# EVK_xA1.net
KiCad netlist of a schematic drawn in Altium Designer
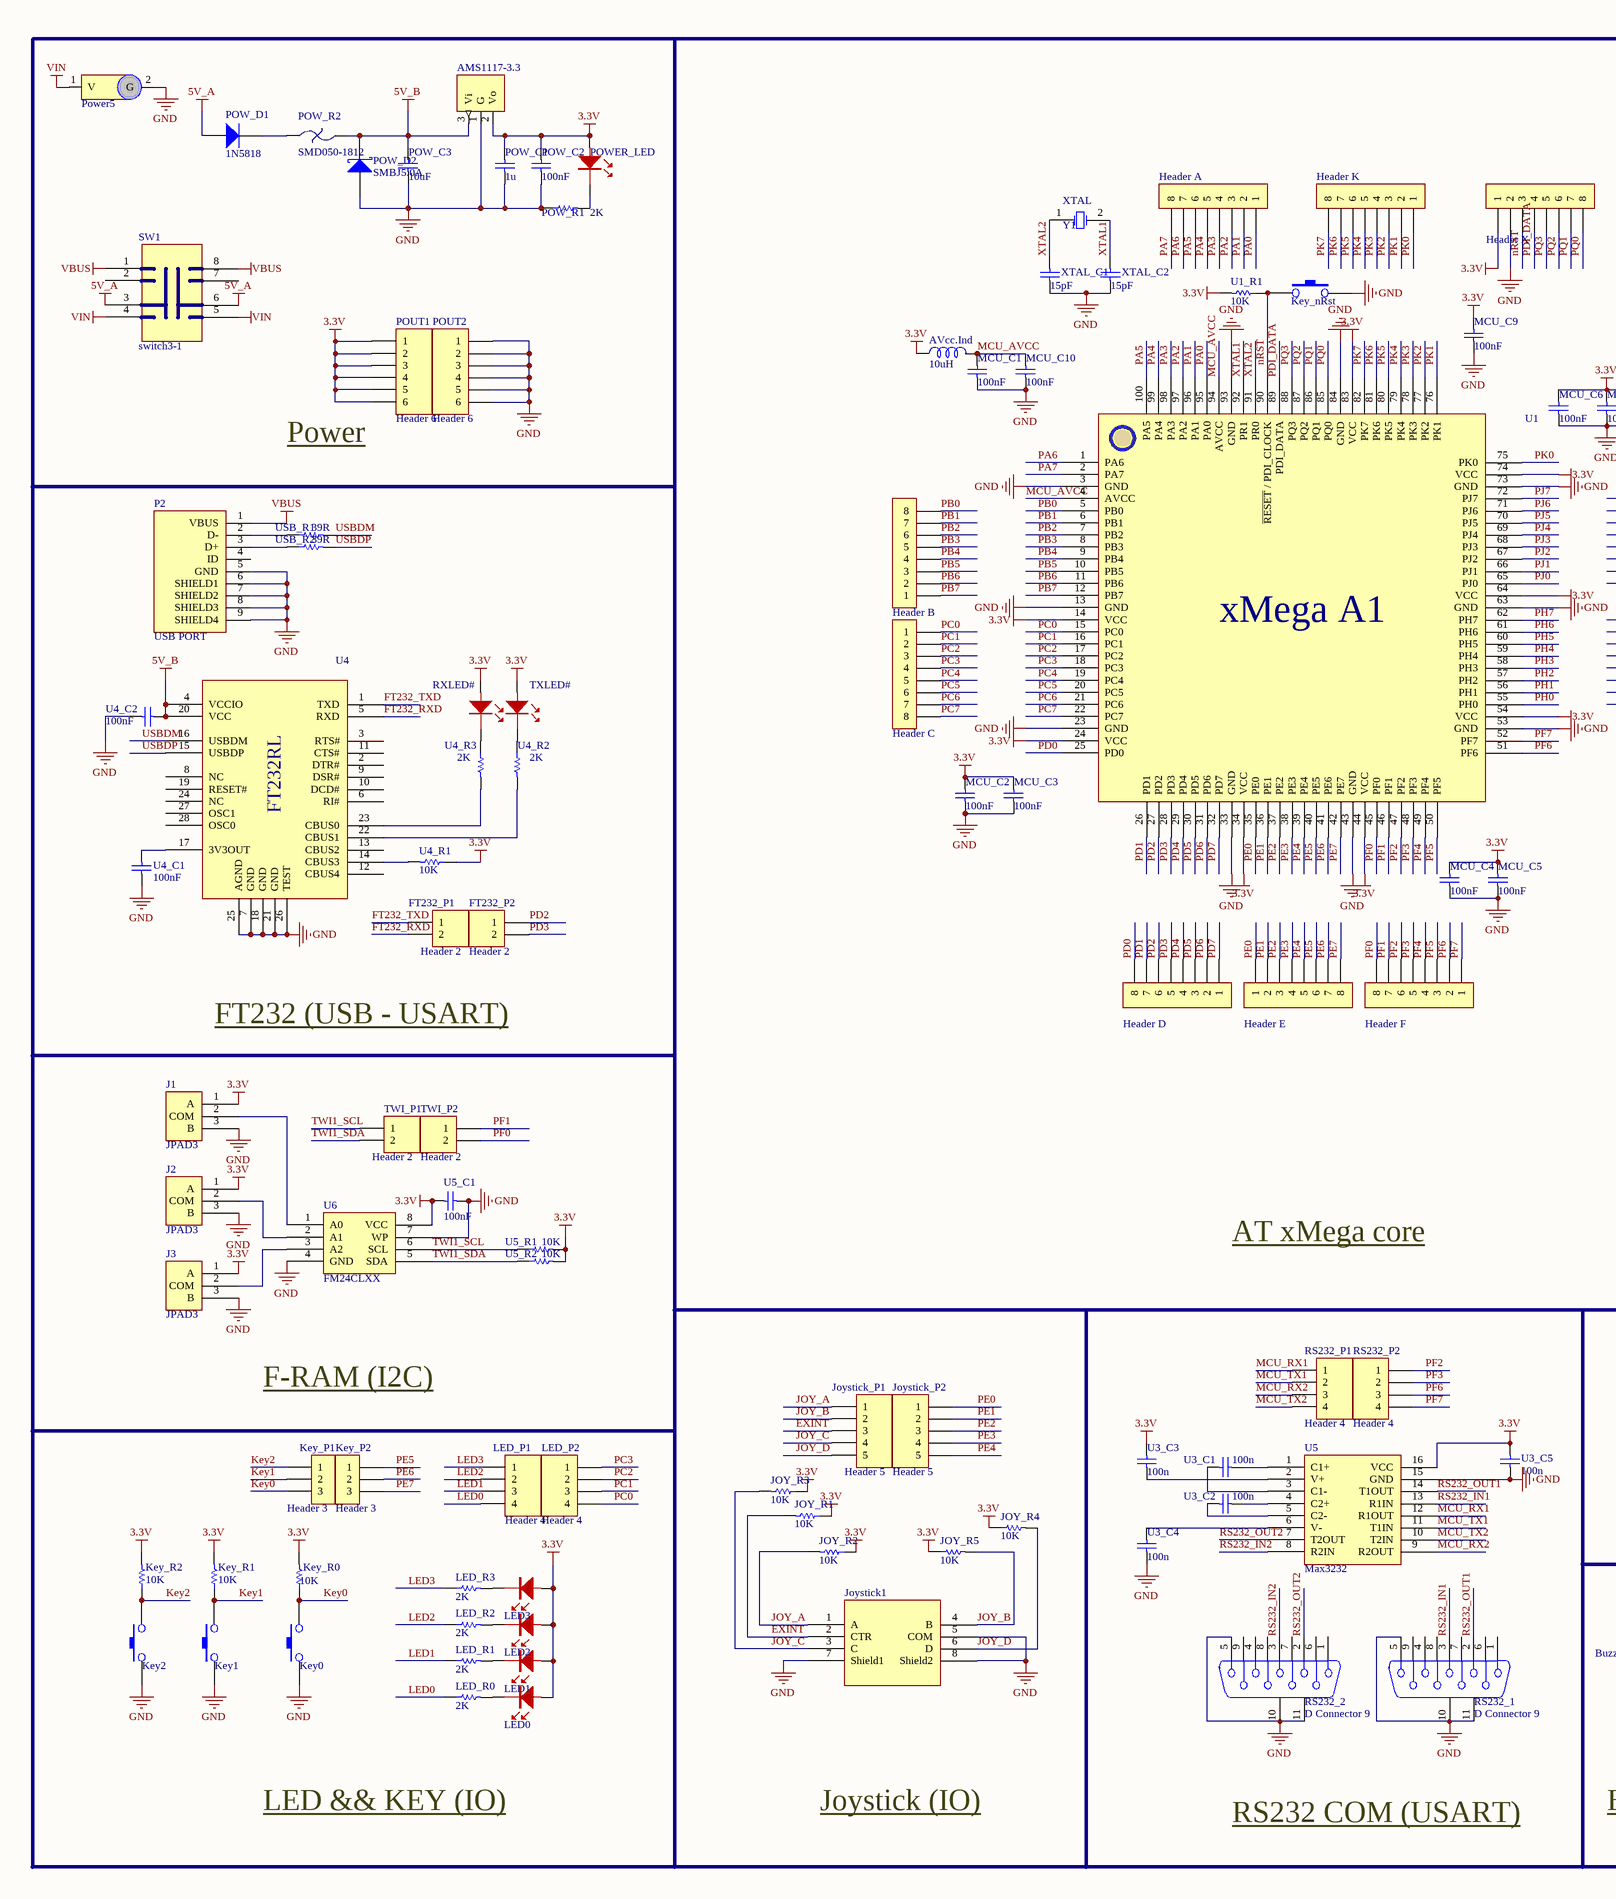
[diagram p0: EVK xA1.SchDoc, left]
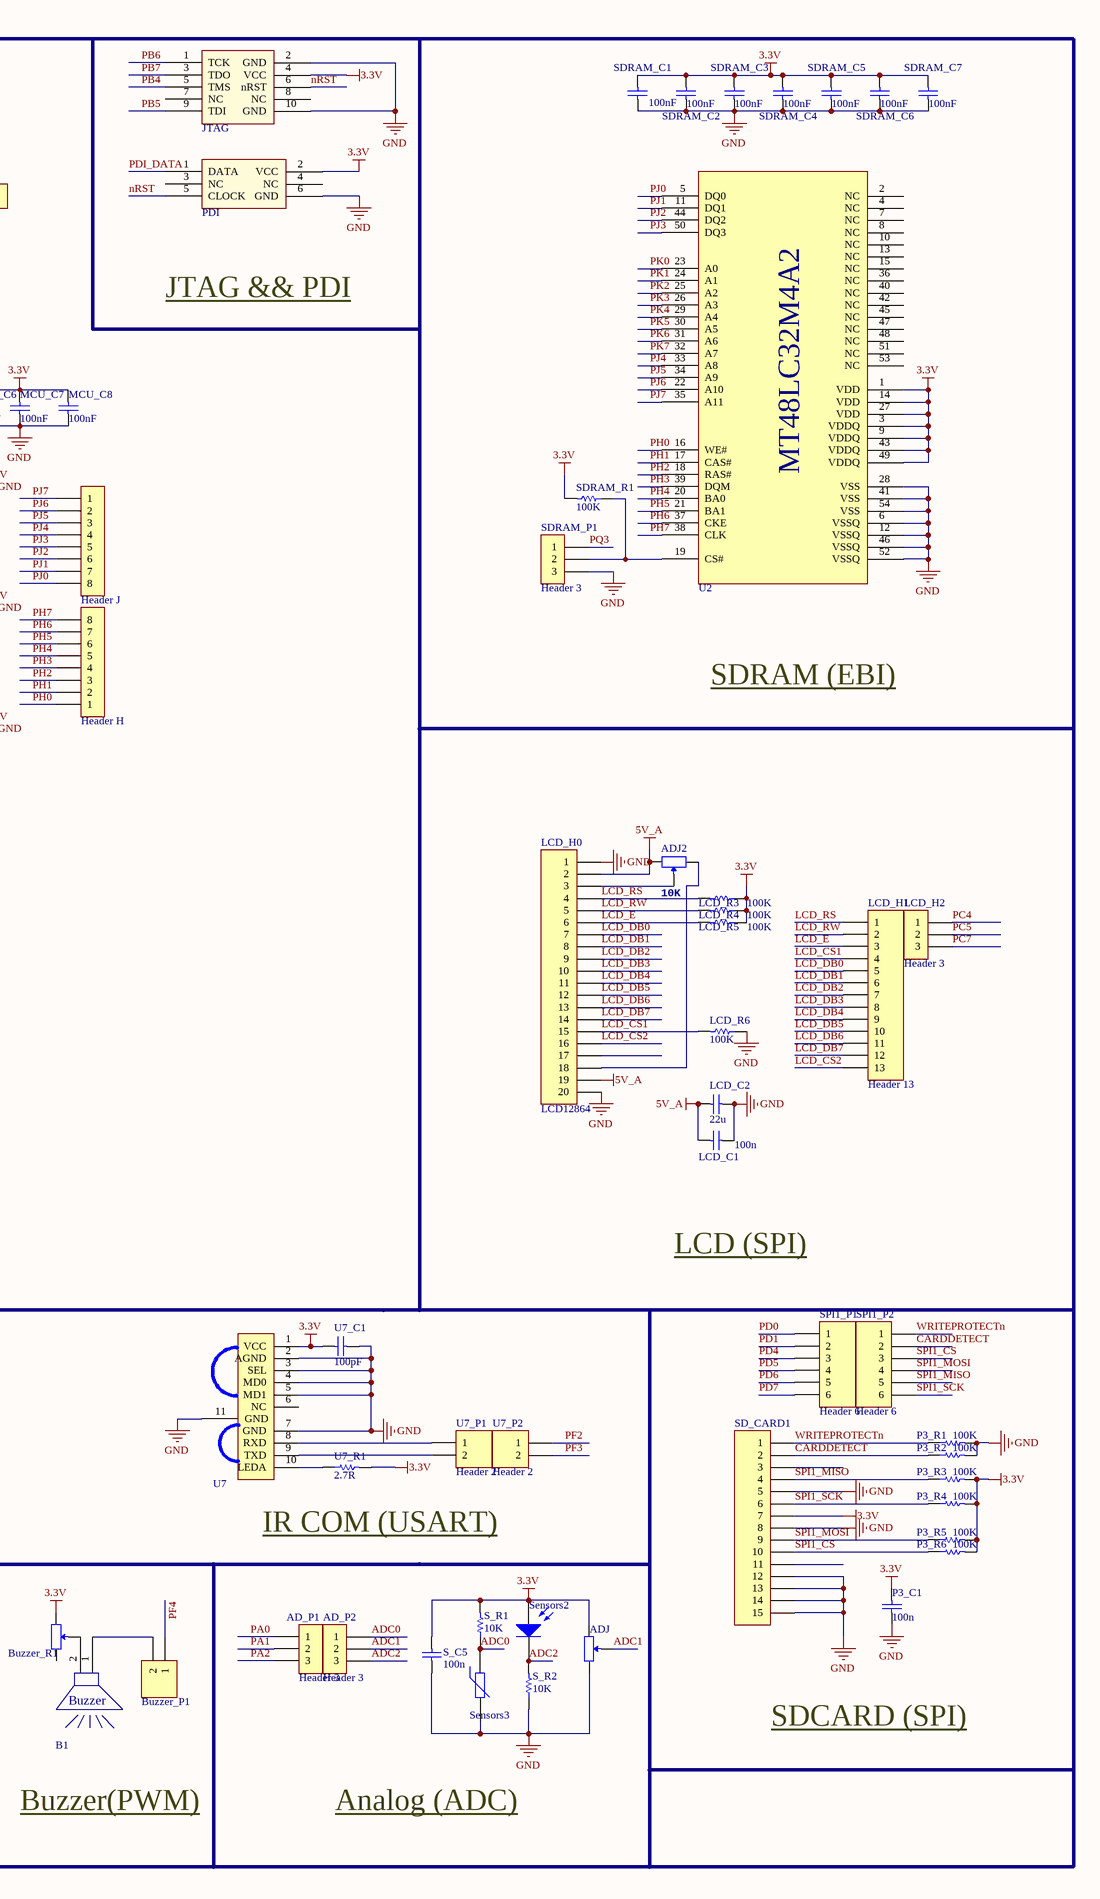
[diagram p1: EVK xA1.SchDoc, right]

(export (version "E")
  (design (tool "Eeschema 10.0.6"))
  (components
    (comp (ref "ADJ") (value "RES_ADJ") (footprint "RESADJ") (libsource (lib "zz") (part "RES_ADJ")))
    (comp (ref "ADJ2") (value "10K") (footprint "RESADJ") (libsource (lib "zz") (part "RES_ADJ")))
    (comp (ref "AD_P1")
      (value "Header 3")
      (footprint "SIP3")
      (description "Header, 3-Pin")
      (libsource (lib "") (part "Header 3_1"))
    )
    (comp (ref "AD_P2")
      (value "Header 3")
      (footprint "SIP3")
      (description "Header, 3-Pin")
      (libsource (lib "zz") (part "Header 3"))
    )
    (comp (ref "AMS1117-3.3")
      (value "LD1117")
      (footprint "LD1117-3.3")
      (libsource (lib "zz") (part "LD1117"))
    )
    (comp (ref "AVcc.Ind") (value "10uH") (footprint "RES") (libsource (lib "zz") (part "IND")))
    (comp (ref "B1") (value "Buzzer") (footprint "buzzer") (libsource (lib "zz") (part "Buzzer")))
    (comp (ref "Buzzer_P1")
      (value "Header 2")
      (footprint "SIP2")
      (description "Header, 2-Pin")
      (fields (field (name "PUBLISHER") "Altium Limited"))
      (libsource (lib "") (part "Header 2_1"))
    )
    (comp (ref "Buzzer_R1") (value "RES_ADJ") (footprint "RESADJ2") (libsource (lib "zz") (part "RES_ADJ")))
    (comp (ref "FT232_P1")
      (value "Header 2")
      (footprint "SIP2")
      (description "Header, 2-Pin")
      (fields (field (name "PUBLISHER") "Altium Limited"))
      (libsource (lib "zz") (part "Header 2"))
    )
    (comp (ref "FT232_P2")
      (value "Header 2")
      (footprint "SIP2")
      (description "Header, 2-Pin")
      (fields (field (name "PUBLISHER") "Altium Limited"))
      (libsource (lib "") (part "Header 2_1"))
    )
    (comp (ref "Header A")
      (value "Header 8")
      (footprint "SIP8")
      (description "Header, 8-Pin")
      (libsource (lib "") (part "Header 8_2"))
    )
    (comp (ref "Header B")
      (value "Header 8")
      (footprint "SIP8")
      (description "Header, 8-Pin")
      (libsource (lib "") (part "Header 8_1"))
    )
    (comp (ref "Header C")
      (value "Header 8")
      (footprint "SIP8")
      (description "Header, 8-Pin")
      (libsource (lib "") (part "Header 8_3"))
    )
    (comp (ref "Header D")
      (value "Header 8")
      (footprint "SIP8")
      (description "Header, 8-Pin")
      (libsource (lib "") (part "Header 8_3"))
    )
    (comp (ref "Header E")
      (value "Header 8")
      (footprint "SIP8")
      (description "Header, 8-Pin")
      (libsource (lib "") (part "Header 8_1"))
    )
    (comp (ref "Header F")
      (value "Header 8")
      (footprint "SIP8")
      (description "Header, 8-Pin")
      (libsource (lib "") (part "Header 8_3"))
    )
    (comp (ref "Header H")
      (value "Header 8")
      (footprint "SIP8")
      (description "Header, 8-Pin")
      (libsource (lib "zz") (part "Header 8"))
    )
    (comp (ref "Header J")
      (value "Header 8")
      (footprint "SIP8")
      (description "Header, 8-Pin")
      (libsource (lib "") (part "Header 8_2"))
    )
    (comp (ref "Header K")
      (value "Header 8")
      (footprint "SIP8")
      (description "Header, 8-Pin")
      (libsource (lib "") (part "Header 8_2"))
    )
    (comp (ref "Header X")
      (value "Header 8")
      (footprint "SIP8")
      (description "Header, 8-Pin")
      (libsource (lib "zz") (part "Header 8"))
    )
    (comp (ref "J1") (value "JPAD3") (footprint "JPAD3") (libsource (lib "zz") (part "JPAD3")))
    (comp (ref "J2") (value "JPAD3") (footprint "JPAD3") (libsource (lib "zz") (part "JPAD3")))
    (comp (ref "J3") (value "JPAD3") (footprint "JPAD3") (libsource (lib "zz") (part "JPAD3")))
    (comp (ref "Joystick1")
      (value "Joystick")
      (footprint "Joystick")
      (libsource (lib "zz") (part "Joystick"))
    )
    (comp (ref "Joystick_P1")
      (value "Header 5")
      (footprint "SIP5")
      (description "Header, 5-Pin")
      (fields (field (name "PUBLISHER") "Altium Limited"))
      (libsource (lib "zz") (part "Header 5"))
    )
    (comp (ref "Joystick_P2")
      (value "Header 5")
      (footprint "SIP5")
      (description "Header, 5-Pin")
      (fields (field (name "PUBLISHER") "Altium Limited"))
      (libsource (lib "") (part "Header 5_1"))
    )
    (comp (ref "JOY_R1")
      (value "10K")
      (footprint "0805")
      (description "Resistor")
      (fields (field (name "Comment") "R_0805"))
      (libsource (lib "zz") (part "R_0805"))
    )
    (comp (ref "JOY_R2")
      (value "10K")
      (footprint "0805")
      (description "Resistor")
      (fields (field (name "Comment") "R_0805"))
      (libsource (lib "zz") (part "R_0805"))
    )
    (comp (ref "JOY_R3")
      (value "10K")
      (footprint "0805")
      (description "Resistor")
      (fields (field (name "Comment") "R_0805"))
      (libsource (lib "zz") (part "R_0805"))
    )
    (comp (ref "JOY_R4")
      (value "10K")
      (footprint "0805")
      (description "Resistor")
      (fields (field (name "Comment") "R_0805"))
      (libsource (lib "zz") (part "R_0805"))
    )
    (comp (ref "JOY_R5")
      (value "10K")
      (footprint "0805")
      (description "Resistor")
      (fields (field (name "Comment") "R_0805"))
      (libsource (lib "zz") (part "R_0805"))
    )
    (comp (ref "JTAG") (value "JTAG") (footprint "ISP_10") (libsource (lib "zz") (part "JTAG")))
    (comp (ref "Key0") (value "PB2") (footprint "KEY") (libsource (lib "zz") (part "KEY")))
    (comp (ref "Key1") (value "PB2") (footprint "KEY") (libsource (lib "zz") (part "KEY")))
    (comp (ref "Key2") (value "PB2") (footprint "KEY") (libsource (lib "zz") (part "KEY")))
    (comp (ref "Key_nRst") (value "PB2") (footprint "KEY") (libsource (lib "zz") (part "KEY")))
    (comp (ref "Key_P1")
      (value "Header 3")
      (footprint "SIP3")
      (description "Header, 3-Pin")
      (libsource (lib "") (part "Header 3_1"))
    )
    (comp (ref "Key_P2")
      (value "Header 3")
      (footprint "SIP3")
      (description "Header, 3-Pin")
      (libsource (lib "zz") (part "Header 3"))
    )
    (comp (ref "Key_R0")
      (value "10K")
      (footprint "0805")
      (description "Resistor")
      (fields (field (name "Comment") "R_0805"))
      (libsource (lib "zz") (part "R_0805"))
    )
    (comp (ref "Key_R1")
      (value "10K")
      (footprint "0805")
      (description "Resistor")
      (fields (field (name "Comment") "R_0805"))
      (libsource (lib "zz") (part "R_0805"))
    )
    (comp (ref "Key_R2")
      (value "10K")
      (footprint "0805")
      (description "Resistor")
      (fields (field (name "Comment") "R_0805"))
      (libsource (lib "zz") (part "R_0805"))
    )
    (comp (ref "LCD_C1")
      (value "100n")
      (footprint "0805")
      (description "Capacitor")
      (fields (field (name "Comment") "C_0805"))
      (libsource (lib "zz") (part "C_0805"))
    )
    (comp (ref "LCD_C2")
      (value "22u")
      (footprint "0805")
      (description "Capacitor")
      (fields (field (name "Comment") "C_0805"))
      (libsource (lib "zz") (part "C_0805"))
    )
    (comp (ref "LCD_H0")
      (value "LCD12864")
      (footprint "SIP20")
      (description "Header, 20-Pin")
      (fields (field (name "PUBLISHER") "Altium Limited"))
      (libsource (lib "zz") (part "Header 20"))
    )
    (comp (ref "LCD_H1")
      (value "Header 13")
      (footprint "SIP13")
      (description "Header, 13-Pin")
      (fields (field (name "PUBLISHER") "Altium Limited"))
      (libsource (lib "zz") (part "Header 13"))
    )
    (comp (ref "LCD_H2")
      (value "Header 3")
      (footprint "SIP3")
      (description "Header, 3-Pin")
      (libsource (lib "zz") (part "Header 3"))
    )
    (comp (ref "LCD_R3")
      (value "100K")
      (footprint "0805")
      (description "Resistor")
      (fields (field (name "Comment") "R_0805"))
      (libsource (lib "zz") (part "R_0805"))
    )
    (comp (ref "LCD_R4")
      (value "100K")
      (footprint "0805")
      (description "Resistor")
      (fields (field (name "Comment") "R_0805"))
      (libsource (lib "zz") (part "R_0805"))
    )
    (comp (ref "LCD_R5")
      (value "100K")
      (footprint "0805")
      (description "Resistor")
      (fields (field (name "Comment") "R_0805"))
      (libsource (lib "zz") (part "R_0805"))
    )
    (comp (ref "LCD_R6")
      (value "100K")
      (footprint "0805")
      (description "Resistor")
      (fields (field (name "Comment") "R_0805"))
      (libsource (lib "zz") (part "R_0805"))
    )
    (comp (ref "LED0") (value "LED_0805") (footprint "0805_LED") (libsource (lib "zz") (part "LED_0805")))
    (comp (ref "LED1") (value "LED_0805") (footprint "0805_LED") (libsource (lib "zz") (part "LED_0805")))
    (comp (ref "LED2") (value "LED_0805") (footprint "0805_LED") (libsource (lib "zz") (part "LED_0805")))
    (comp (ref "LED3") (value "LED_0805") (footprint "0805_LED") (libsource (lib "zz") (part "LED_0805")))
    (comp (ref "LED_P1")
      (value "Header 4")
      (footprint "SIP4")
      (description "Header, 4-Pin")
      (fields (field (name "PUBLISHER") "Altium Limited"))
      (libsource (lib "zz") (part "Header 4"))
    )
    (comp (ref "LED_P2")
      (value "Header 4")
      (footprint "SIP4")
      (description "Header, 4-Pin")
      (fields (field (name "PUBLISHER") "Altium Limited"))
      (libsource (lib "") (part "Header 4_1"))
    )
    (comp (ref "LED_R0")
      (value "2K")
      (footprint "0805")
      (description "Resistor")
      (fields (field (name "Comment") "R_0805"))
      (libsource (lib "zz") (part "R_0805"))
    )
    (comp (ref "LED_R1")
      (value "2K")
      (footprint "0805")
      (description "Resistor")
      (fields (field (name "Comment") "R_0805"))
      (libsource (lib "zz") (part "R_0805"))
    )
    (comp (ref "LED_R2")
      (value "2K")
      (footprint "0805")
      (description "Resistor")
      (fields (field (name "Comment") "R_0805"))
      (libsource (lib "zz") (part "R_0805"))
    )
    (comp (ref "LED_R3")
      (value "2K")
      (footprint "0805")
      (description "Resistor")
      (fields (field (name "Comment") "R_0805"))
      (libsource (lib "zz") (part "R_0805"))
    )
    (comp (ref "MCU_C1")
      (value "100nF")
      (footprint "0805")
      (description "Capacitor")
      (fields (field (name "Comment") "C_0805"))
      (libsource (lib "zz") (part "C_0805"))
    )
    (comp (ref "MCU_C2")
      (value "100nF")
      (footprint "0805")
      (description "Capacitor")
      (fields (field (name "Comment") "C_0805"))
      (libsource (lib "zz") (part "C_0805"))
    )
    (comp (ref "MCU_C3")
      (value "100nF")
      (footprint "0805")
      (description "Capacitor")
      (fields (field (name "Comment") "C_0805"))
      (libsource (lib "zz") (part "C_0805"))
    )
    (comp (ref "MCU_C4")
      (value "100nF")
      (footprint "0805")
      (description "Capacitor")
      (fields (field (name "Comment") "C_0805"))
      (libsource (lib "zz") (part "C_0805"))
    )
    (comp (ref "MCU_C5")
      (value "100nF")
      (footprint "0805")
      (description "Capacitor")
      (fields (field (name "Comment") "C_0805"))
      (libsource (lib "zz") (part "C_0805"))
    )
    (comp (ref "MCU_C6")
      (value "100nF")
      (footprint "0805")
      (description "Capacitor")
      (fields (field (name "Comment") "C_0805"))
      (libsource (lib "zz") (part "C_0805"))
    )
    (comp (ref "MCU_C7")
      (value "100nF")
      (footprint "0805")
      (description "Capacitor")
      (fields (field (name "Comment") "C_0805"))
      (libsource (lib "zz") (part "C_0805"))
    )
    (comp (ref "MCU_C8")
      (value "100nF")
      (footprint "0805")
      (description "Capacitor")
      (fields (field (name "Comment") "C_0805"))
      (libsource (lib "zz") (part "C_0805"))
    )
    (comp (ref "MCU_C9")
      (value "100nF")
      (footprint "0805")
      (description "Capacitor")
      (fields (field (name "Comment") "C_0805"))
      (libsource (lib "zz") (part "C_0805"))
    )
    (comp (ref "MCU_C10")
      (value "100nF")
      (footprint "0805")
      (description "Capacitor")
      (fields (field (name "Comment") "C_0805"))
      (libsource (lib "zz") (part "C_0805"))
    )
    (comp (ref "P2") (value "USB PORT") (footprint "USB2") (libsource (lib "zz") (part "USB")))
    (comp (ref "P3_C1")
      (value "100n")
      (footprint "0805")
      (description "Capacitor")
      (fields (field (name "Comment") "C_0805"))
      (libsource (lib "zz") (part "C_0805"))
    )
    (comp (ref "P3_R1")
      (value "100K")
      (footprint "0805")
      (description "Resistor")
      (fields (field (name "Comment") "R_0805"))
      (libsource (lib "zz") (part "R_0805"))
    )
    (comp (ref "P3_R2")
      (value "100K")
      (footprint "0805")
      (description "Resistor")
      (fields (field (name "Comment") "R_0805"))
      (libsource (lib "zz") (part "R_0805"))
    )
    (comp (ref "P3_R3")
      (value "100K")
      (footprint "0805")
      (description "Resistor")
      (fields (field (name "Comment") "R_0805"))
      (libsource (lib "zz") (part "R_0805"))
    )
    (comp (ref "P3_R4")
      (value "100K")
      (footprint "0805")
      (description "Resistor")
      (fields (field (name "Comment") "R_0805"))
      (libsource (lib "zz") (part "R_0805"))
    )
    (comp (ref "P3_R5")
      (value "100K")
      (footprint "0805")
      (description "Resistor")
      (fields (field (name "Comment") "R_0805"))
      (libsource (lib "zz") (part "R_0805"))
    )
    (comp (ref "P3_R6")
      (value "100K")
      (footprint "0805")
      (description "Resistor")
      (fields (field (name "Comment") "R_0805"))
      (libsource (lib "zz") (part "R_0805"))
    )
    (comp (ref "PDI") (value "PDI") (footprint "ISP_6") (libsource (lib "zz") (part "PDI")))
    (comp (ref "POUT1")
      (value "Header 6")
      (footprint "SIP6")
      (description "Header, 6-Pin")
      (fields (field (name "PUBLISHER") "Altium Limited"))
      (libsource (lib "") (part "Header 6_1"))
    )
    (comp (ref "POUT2")
      (value "Header 6")
      (footprint "SIP6")
      (description "Header, 6-Pin")
      (fields (field (name "PUBLISHER") "Altium Limited"))
      (libsource (lib "zz") (part "Header 6"))
    )
    (comp (ref "Power5")
      (value "5V")
      (footprint "PWR_5V")
      (description "Power5")
      (libsource (lib "zz") (part "Power5"))
    )
    (comp (ref "POWER_LED")
      (value "LED_0805")
      (footprint "0805_LED")
      (libsource (lib "zz") (part "LED_0805"))
    )
    (comp (ref "POW_C1")
      (value "1u")
      (footprint "0805")
      (description "Capacitor")
      (fields (field (name "Comment") "C_0805"))
      (libsource (lib "zz") (part "C_0805"))
    )
    (comp (ref "POW_C2")
      (value "100nF")
      (footprint "0805")
      (description "Capacitor")
      (fields (field (name "Comment") "C_0805"))
      (libsource (lib "zz") (part "C_0805"))
    )
    (comp (ref "POW_C3")
      (value "10uF")
      (footprint "0805")
      (description "Capacitor")
      (fields (field (name "Comment") "C_0805"))
      (libsource (lib "zz") (part "C_0805"))
    )
    (comp (ref "POW_D1")
      (value "1N5818")
      (footprint "diode")
      (description "1 Amp General Purpose Rectifier")
      (libsource (lib "zz") (part "Diode 1N"))
    )
    (comp (ref "POW_D2") (value "SMBJ5.0A") (footprint "SMBJ") (libsource (lib "zz") (part "SMBJ5.0A")))
    (comp (ref "POW_R1")
      (value "2K")
      (footprint "0805")
      (description "Resistor")
      (fields (field (name "Comment") "R_0805"))
      (libsource (lib "zz") (part "R_0805"))
    )
    (comp (ref "POW_R2")
      (value "SMD050-1812")
      (footprint "SMD-1812")
      (libsource (lib "zz") (part "SMD050-1812"))
    )
    (comp (ref "RS232_1")
      (value "D Connector 9")
      (footprint "DB9_2")
      (description "Receptacle Assembly, 9 Position, Right Angle")
      (libsource (lib "zz") (part "D Connector 9"))
    )
    (comp (ref "RS232_2")
      (value "D Connector 9")
      (footprint "DB9_2")
      (description "Receptacle Assembly, 9 Position, Right Angle")
      (libsource (lib "zz") (part "D Connector 9"))
    )
    (comp (ref "RS232_P1")
      (value "Header 4")
      (footprint "SIP4")
      (description "Header, 4-Pin")
      (fields (field (name "PUBLISHER") "Altium Limited"))
      (libsource (lib "zz") (part "Header 4"))
    )
    (comp (ref "RS232_P2")
      (value "Header 4")
      (footprint "SIP4")
      (description "Header, 4-Pin")
      (fields (field (name "PUBLISHER") "Altium Limited"))
      (libsource (lib "") (part "Header 4_1"))
    )
    (comp (ref "RXLED#") (value "LED_0805") (footprint "0805_LED") (libsource (lib "zz") (part "LED_0805")))
    (comp (ref "SDRAM_C1")
      (value "100nF")
      (footprint "0805")
      (description "Capacitor")
      (fields (field (name "Comment") "C_0805"))
      (libsource (lib "zz") (part "C_0805"))
    )
    (comp (ref "SDRAM_C2")
      (value "100nF")
      (footprint "0805")
      (description "Capacitor")
      (fields (field (name "Comment") "C_0805"))
      (libsource (lib "zz") (part "C_0805"))
    )
    (comp (ref "SDRAM_C3")
      (value "100nF")
      (footprint "0805")
      (description "Capacitor")
      (fields (field (name "Comment") "C_0805"))
      (libsource (lib "zz") (part "C_0805"))
    )
    (comp (ref "SDRAM_C4")
      (value "100nF")
      (footprint "0805")
      (description "Capacitor")
      (fields (field (name "Comment") "C_0805"))
      (libsource (lib "zz") (part "C_0805"))
    )
    (comp (ref "SDRAM_C5")
      (value "100nF")
      (footprint "0805")
      (description "Capacitor")
      (fields (field (name "Comment") "C_0805"))
      (libsource (lib "zz") (part "C_0805"))
    )
    (comp (ref "SDRAM_C6")
      (value "100nF")
      (footprint "0805")
      (description "Capacitor")
      (fields (field (name "Comment") "C_0805"))
      (libsource (lib "zz") (part "C_0805"))
    )
    (comp (ref "SDRAM_C7")
      (value "100nF")
      (footprint "0805")
      (description "Capacitor")
      (fields (field (name "Comment") "C_0805"))
      (libsource (lib "zz") (part "C_0805"))
    )
    (comp (ref "SDRAM_P1")
      (value "Header 3")
      (footprint "SIP3")
      (description "Header, 3-Pin")
      (libsource (lib "zz") (part "Header 3"))
    )
    (comp (ref "SDRAM_R1")
      (value "100K")
      (footprint "0805")
      (description "Resistor")
      (fields (field (name "Comment") "R_0603"))
      (libsource (lib "zz") (part "R_0603"))
    )
    (comp (ref "SD_CARD1")
      (value "SDCARD")
      (footprint "SDK")
      (description "Header, 15-Pin")
      (libsource (lib "zz") (part "SDCARD"))
    )
    (comp (ref "Sensors2")
      (value "Photo Sen")
      (footprint "LED")
      (description "Photosensitive Diode")
      (libsource (lib "Miscellaneous Devices") (part "Photo Sen"))
    )
    (comp (ref "Sensors3")
      (value "Res Varistor")
      (footprint "diode")
      (description "Varistor (Voltage-Sensitive Resistor)")
      (libsource (lib "Miscellaneous Devices") (part "Res Varistor"))
    )
    (comp (ref "SPI1_P1")
      (value "Header 6")
      (footprint "SIP6")
      (description "Header, 6-Pin")
      (fields (field (name "PUBLISHER") "Altium Limited"))
      (libsource (lib "") (part "Header 6_1"))
    )
    (comp (ref "SPI1_P2")
      (value "Header 6")
      (footprint "SIP6")
      (description "Header, 6-Pin")
      (fields (field (name "PUBLISHER") "Altium Limited"))
      (libsource (lib "zz") (part "Header 6"))
    )
    (comp (ref "SW1") (value "switch3-1") (footprint "Switch3-1") (libsource (lib "zz") (part "switch3-1")))
    (comp (ref "S_C5")
      (value "100n")
      (footprint "0805")
      (description "Capacitor")
      (fields (field (name "Comment") "C_0805"))
      (libsource (lib "zz") (part "C_0805"))
    )
    (comp (ref "S_R1")
      (value "10K")
      (footprint "0805")
      (description "Resistor")
      (fields (field (name "Comment") "R_0805"))
      (libsource (lib "zz") (part "R_0805"))
    )
    (comp (ref "S_R2")
      (value "10K")
      (footprint "0805")
      (description "Resistor")
      (fields (field (name "Comment") "R_0805"))
      (libsource (lib "zz") (part "R_0805"))
    )
    (comp (ref "TWI_P1")
      (value "Header 2")
      (footprint "SIP2")
      (description "Header, 2-Pin")
      (fields (field (name "PUBLISHER") "Altium Limited"))
      (libsource (lib "zz") (part "Header 2"))
    )
    (comp (ref "TWI_P2")
      (value "Header 2")
      (footprint "SIP2")
      (description "Header, 2-Pin")
      (fields (field (name "PUBLISHER") "Altium Limited"))
      (libsource (lib "") (part "Header 2_1"))
    )
    (comp (ref "TXLED#") (value "LED_0805") (footprint "0805_LED") (libsource (lib "zz") (part "LED_0805")))
    (comp (ref "U1") (value "xMega A1") (footprint "TQFP100 CORE") (libsource (lib "zz") (part "xMega A1")))
    (comp (ref "U1_R1")
      (value "10K")
      (footprint "0805")
      (description "Resistor")
      (fields (field (name "Comment") "R_0805"))
      (libsource (lib "zz") (part "R_0805"))
    )
    (comp (ref "U2") (value "MT48LC32M4A2") (footprint "TSOP54") (libsource (lib "zz") (part "MT48LC32M4A2")))
    (comp (ref "U3_C1")
      (value "100n")
      (footprint "0805")
      (description "Capacitor")
      (fields (field (name "Comment") "C_0805"))
      (libsource (lib "zz") (part "C_0805"))
    )
    (comp (ref "U3_C2")
      (value "100n")
      (footprint "0805")
      (description "Capacitor")
      (fields (field (name "Comment") "C_0805"))
      (libsource (lib "zz") (part "C_0805"))
    )
    (comp (ref "U3_C3")
      (value "100n")
      (footprint "0805")
      (description "Capacitor")
      (fields (field (name "Comment") "C_0805"))
      (libsource (lib "zz") (part "C_0805"))
    )
    (comp (ref "U3_C4")
      (value "100n")
      (footprint "0805")
      (description "Capacitor")
      (fields (field (name "Comment") "C_0805"))
      (libsource (lib "zz") (part "C_0805"))
    )
    (comp (ref "U3_C5")
      (value "100n")
      (footprint "0805")
      (description "Capacitor")
      (fields (field (name "Comment") "C_0805"))
      (libsource (lib "zz") (part "C_0805"))
    )
    (comp (ref "U4") (value "FT232RL") (footprint "SSOP28") (libsource (lib "zz") (part "FT232RL")))
    (comp (ref "U4_C1")
      (value "100nF")
      (footprint "0805")
      (description "Capacitor")
      (fields (field (name "Comment") "C_0805"))
      (libsource (lib "zz") (part "C_0805"))
    )
    (comp (ref "U4_C2")
      (value "100nF")
      (footprint "0805")
      (description "Capacitor")
      (fields (field (name "Comment") "C_0805"))
      (libsource (lib "zz") (part "C_0805"))
    )
    (comp (ref "U4_R1")
      (value "10K")
      (footprint "0805")
      (description "Resistor")
      (fields (field (name "Comment") "R_0805"))
      (libsource (lib "zz") (part "R_0805"))
    )
    (comp (ref "U4_R2")
      (value "2K")
      (footprint "0805")
      (description "Resistor")
      (fields (field (name "Comment") "R_0805"))
      (libsource (lib "zz") (part "R_0805"))
    )
    (comp (ref "U4_R3")
      (value "2K")
      (footprint "0805")
      (description "Resistor")
      (fields (field (name "Comment") "R_0805"))
      (libsource (lib "zz") (part "R_0805"))
    )
    (comp (ref "U5") (value "Max3232") (footprint "SOP16") (libsource (lib "zz") (part "Max3232")))
    (comp (ref "U5_C1")
      (value "100nF")
      (footprint "0805")
      (description "Capacitor")
      (fields (field (name "Comment") "C_0805"))
      (libsource (lib "zz") (part "C_0805"))
    )
    (comp (ref "U5_R1")
      (value "10K")
      (footprint "0805")
      (description "Resistor")
      (fields (field (name "Comment") "R_0805"))
      (libsource (lib "zz") (part "R_0805"))
    )
    (comp (ref "U5_R2")
      (value "10K")
      (footprint "0805")
      (description "Resistor")
      (fields (field (name "Comment") "R_0805"))
      (libsource (lib "zz") (part "R_0805"))
    )
    (comp (ref "U6") (value "FM24CLXX") (footprint "AT24C") (libsource (lib "zz") (part "AT24C")))
    (comp (ref "U7")
      (value "HSDL-3602-007")
      (footprint "HSDL-3602-007")
      (libsource (lib "zz") (part "HSDL-3602-007"))
    )
    (comp (ref "U7_C1")
      (value "100pF")
      (footprint "0805")
      (description "Capacitor")
      (fields (field (name "Comment") "C_0805"))
      (libsource (lib "zz") (part "C_0805"))
    )
    (comp (ref "U7_P1")
      (value "Header 2")
      (footprint "SIP2")
      (description "Header, 2-Pin")
      (fields (field (name "PUBLISHER") "Altium Limited"))
      (libsource (lib "zz") (part "Header 2"))
    )
    (comp (ref "U7_P2")
      (value "Header 2")
      (footprint "SIP2")
      (description "Header, 2-Pin")
      (fields (field (name "PUBLISHER") "Altium Limited"))
      (libsource (lib "") (part "Header 2_1"))
    )
    (comp (ref "U7_R1")
      (value "2.7R")
      (footprint "0805")
      (description "Resistor")
      (fields (field (name "Comment") "R_0805"))
      (libsource (lib "zz") (part "R_0805"))
    )
    (comp (ref "USB_R1")
      (value "39R")
      (footprint "0805")
      (description "Resistor")
      (fields (field (name "Comment") "R_0805"))
      (libsource (lib "zz") (part "R_0805"))
    )
    (comp (ref "USB_R2")
      (value "39R")
      (footprint "0805")
      (description "Resistor")
      (fields (field (name "Comment") "R_0805"))
      (libsource (lib "zz") (part "R_0805"))
    )
    (comp (ref "XTAL_C1")
      (value "15pF")
      (footprint "0805")
      (description "Capacitor")
      (fields (field (name "Comment") "Cap"))
      (libsource (lib "Miscellaneous Devices") (part "Cap"))
    )
    (comp (ref "XTAL_C2")
      (value "15pF")
      (footprint "0805")
      (description "Capacitor")
      (fields (field (name "Comment") "Cap"))
      (libsource (lib "Miscellaneous Devices") (part "Cap"))
    )
    (comp (ref "Y1")
      (value "XTAL")
      (footprint "CRYSTAL")
      (description "Crystal Oscillator")
      (fields (field (name "PUBLISHER") "Altium Limited"))
      (libsource (lib "zz") (part "XTAL"))
    )
  )
  (nets
    (net (code "1") (name "/ADC0") (class "Default")
      (node (ref "AD_P2") (pin "1") (pinfunction "1_1") (pintype "passive"))
      (node (ref "S_R1") (pin "1") (pinfunction "1_1") (pintype "passive"))
      (node (ref "Sensors3") (pin "1") (pinfunction "1_1") (pintype "passive"))
    )
    (net (code "2") (name "/ADC1") (class "Default")
      (node (ref "ADJ") (pin "2") (pinfunction "TAP_2") (pintype "passive"))
      (node (ref "AD_P2") (pin "2") (pinfunction "2_2") (pintype "passive"))
    )
    (net (code "3") (name "/ADC2") (class "Default")
      (node (ref "AD_P2") (pin "3") (pinfunction "3_3") (pintype "passive"))
      (node (ref "S_R2") (pin "2") (pinfunction "2_2") (pintype "passive"))
      (node (ref "Sensors2") (pin "2") (pinfunction "K_2") (pintype "passive"))
    )
    (net (code "4") (name "/CARDDETECT") (class "Default")
      (node (ref "P3_R2") (pin "1") (pinfunction "1_1") (pintype "passive"))
      (node (ref "SD_CARD1") (pin "2") (pinfunction "2_2") (pintype "passive"))
      (node (ref "SPI1_P2") (pin "2") (pinfunction "2_2") (pintype "passive"))
    )
    (net (code "5") (name "/EXINT") (class "Default")
      (node (ref "JOY_R1") (pin "2") (pinfunction "2_2") (pintype "passive"))
      (node (ref "Joystick1") (pin "2") (pinfunction "CTR_2") (pintype "passive"))
      (node (ref "Joystick_P1") (pin "3") (pinfunction "3_3") (pintype "passive"))
    )
    (net (code "6") (name "/FT232_RXD") (class "Default")
      (node (ref "FT232_P1") (pin "2") (pinfunction "2_2") (pintype "passive"))
      (node (ref "U4") (pin "5") (pinfunction "RXD_5") (pintype "passive"))
    )
    (net (code "7") (name "/FT232_TXD") (class "Default")
      (node (ref "FT232_P1") (pin "1") (pinfunction "1_1") (pintype "passive"))
      (node (ref "U4") (pin "1") (pinfunction "TXD_1") (pintype "passive"))
    )
    (net (code "8") (name "/JOY_A") (class "Default")
      (node (ref "JOY_R2") (pin "2") (pinfunction "2_2") (pintype "passive"))
      (node (ref "Joystick1") (pin "1") (pinfunction "A_1") (pintype "passive"))
      (node (ref "Joystick_P1") (pin "1") (pinfunction "1_1") (pintype "passive"))
    )
    (net (code "9") (name "/JOY_B") (class "Default")
      (node (ref "JOY_R5") (pin "2") (pinfunction "2_2") (pintype "passive"))
      (node (ref "Joystick1") (pin "4") (pinfunction "B_4") (pintype "passive"))
      (node (ref "Joystick_P1") (pin "2") (pinfunction "2_2") (pintype "passive"))
    )
    (net (code "10") (name "/JOY_C") (class "Default")
      (node (ref "JOY_R3") (pin "2") (pinfunction "2_2") (pintype "passive"))
      (node (ref "Joystick1") (pin "3") (pinfunction "C_3") (pintype "passive"))
      (node (ref "Joystick_P1") (pin "4") (pinfunction "4_4") (pintype "passive"))
    )
    (net (code "11") (name "/JOY_D") (class "Default")
      (node (ref "JOY_R4") (pin "2") (pinfunction "2_2") (pintype "passive"))
      (node (ref "Joystick1") (pin "6") (pinfunction "D_6") (pintype "passive"))
      (node (ref "Joystick_P1") (pin "5") (pinfunction "5_5") (pintype "passive"))
    )
    (net (code "12") (name "/Key0") (class "Default")
      (node (ref "Key0") (pin "2") (pinfunction "2_2") (pintype "passive"))
      (node (ref "Key_P1") (pin "3") (pinfunction "3_3") (pintype "passive"))
      (node (ref "Key_R0") (pin "1") (pinfunction "1_1") (pintype "passive"))
    )
    (net (code "13") (name "/Key1") (class "Default")
      (node (ref "Key1") (pin "2") (pinfunction "2_2") (pintype "passive"))
      (node (ref "Key_P1") (pin "2") (pinfunction "2_2") (pintype "passive"))
      (node (ref "Key_R1") (pin "1") (pinfunction "1_1") (pintype "passive"))
    )
    (net (code "14") (name "/Key2") (class "Default")
      (node (ref "Key2") (pin "2") (pinfunction "2_2") (pintype "passive"))
      (node (ref "Key_P1") (pin "1") (pinfunction "1_1") (pintype "passive"))
      (node (ref "Key_R2") (pin "1") (pinfunction "1_1") (pintype "passive"))
    )
    (net (code "15") (name "/LCD_CS1") (class "Default")
      (node (ref "LCD_H0") (pin "15") (pinfunction "15_15") (pintype "passive"))
      (node (ref "LCD_H1") (pin "4") (pinfunction "4_4") (pintype "passive"))
      (node (ref "LCD_R6") (pin "2") (pinfunction "2_2") (pintype "passive"))
    )
    (net (code "16") (name "/LCD_CS2") (class "Default")
      (node (ref "LCD_H0") (pin "16") (pinfunction "16_16") (pintype "passive"))
      (node (ref "LCD_H1") (pin "13") (pinfunction "13_13") (pintype "passive"))
    )
    (net (code "17") (name "/LCD_DB0") (class "Default")
      (node (ref "LCD_H0") (pin "7") (pinfunction "7_7") (pintype "passive"))
      (node (ref "LCD_H1") (pin "5") (pinfunction "5_5") (pintype "passive"))
    )
    (net (code "18") (name "/LCD_DB1") (class "Default")
      (node (ref "LCD_H0") (pin "8") (pinfunction "8_8") (pintype "passive"))
      (node (ref "LCD_H1") (pin "6") (pinfunction "6_6") (pintype "passive"))
    )
    (net (code "19") (name "/LCD_DB2") (class "Default")
      (node (ref "LCD_H0") (pin "9") (pinfunction "9_9") (pintype "passive"))
      (node (ref "LCD_H1") (pin "7") (pinfunction "7_7") (pintype "passive"))
    )
    (net (code "20") (name "/LCD_DB3") (class "Default")
      (node (ref "LCD_H0") (pin "10") (pinfunction "10_10") (pintype "passive"))
      (node (ref "LCD_H1") (pin "8") (pinfunction "8_8") (pintype "passive"))
    )
    (net (code "21") (name "/LCD_DB4") (class "Default")
      (node (ref "LCD_H0") (pin "11") (pinfunction "11_11") (pintype "passive"))
      (node (ref "LCD_H1") (pin "9") (pinfunction "9_9") (pintype "passive"))
    )
    (net (code "22") (name "/LCD_DB5") (class "Default")
      (node (ref "LCD_H0") (pin "12") (pinfunction "12_12") (pintype "passive"))
      (node (ref "LCD_H1") (pin "10") (pinfunction "10_10") (pintype "passive"))
    )
    (net (code "23") (name "/LCD_DB6") (class "Default")
      (node (ref "LCD_H0") (pin "13") (pinfunction "13_13") (pintype "passive"))
      (node (ref "LCD_H1") (pin "11") (pinfunction "11_11") (pintype "passive"))
    )
    (net (code "24") (name "/LCD_DB7") (class "Default")
      (node (ref "LCD_H0") (pin "14") (pinfunction "14_14") (pintype "passive"))
      (node (ref "LCD_H1") (pin "12") (pinfunction "12_12") (pintype "passive"))
    )
    (net (code "25") (name "/LCD_E") (class "Default")
      (node (ref "LCD_H0") (pin "6") (pinfunction "6_6") (pintype "passive"))
      (node (ref "LCD_H1") (pin "3") (pinfunction "3_3") (pintype "passive"))
      (node (ref "LCD_R5") (pin "2") (pinfunction "2_2") (pintype "passive"))
    )
    (net (code "26") (name "/LCD_RS") (class "Default")
      (node (ref "LCD_H0") (pin "4") (pinfunction "4_4") (pintype "passive"))
      (node (ref "LCD_H1") (pin "1") (pinfunction "1_1") (pintype "passive"))
      (node (ref "LCD_R3") (pin "2") (pinfunction "2_2") (pintype "passive"))
    )
    (net (code "27") (name "/LCD_RW") (class "Default")
      (node (ref "LCD_H0") (pin "5") (pinfunction "5_5") (pintype "passive"))
      (node (ref "LCD_H1") (pin "2") (pinfunction "2_2") (pintype "passive"))
      (node (ref "LCD_R4") (pin "2") (pinfunction "2_2") (pintype "passive"))
    )
    (net (code "28") (name "/LED0") (class "Default")
      (node (ref "LED_P1") (pin "4") (pinfunction "4_4") (pintype "passive"))
      (node (ref "LED_R0") (pin "1") (pinfunction "1_1") (pintype "passive"))
    )
    (net (code "29") (name "/LED1") (class "Default")
      (node (ref "LED_P1") (pin "3") (pinfunction "3_3") (pintype "passive"))
      (node (ref "LED_R1") (pin "1") (pinfunction "1_1") (pintype "passive"))
    )
    (net (code "30") (name "/LED2") (class "Default")
      (node (ref "LED_P1") (pin "2") (pinfunction "2_2") (pintype "passive"))
      (node (ref "LED_R2") (pin "1") (pinfunction "1_1") (pintype "passive"))
    )
    (net (code "31") (name "/LED3") (class "Default")
      (node (ref "LED_P1") (pin "1") (pinfunction "1_1") (pintype "passive"))
      (node (ref "LED_R3") (pin "1") (pinfunction "1_1") (pintype "passive"))
    )
    (net (code "32") (name "/MCU_AVCC") (class "Default")
      (node (ref "AVcc.Ind") (pin "2") (pinfunction "1_2") (pintype "passive"))
      (node (ref "MCU_C1") (pin "2") (pinfunction "2_2") (pintype "passive"))
      (node (ref "MCU_C10") (pin "2") (pinfunction "2_2") (pintype "passive"))
      (node (ref "U1") (pin "4") (pinfunction "AVCC_4") (pintype "passive"))
      (node (ref "U1") (pin "94") (pinfunction "AVCC_94") (pintype "passive"))
    )
    (net (code "33") (name "/MCU_RX1") (class "Default")
      (node (ref "RS232_P1") (pin "1") (pinfunction "1_1") (pintype "passive"))
      (node (ref "U5") (pin "12") (pinfunction "R1OUT_12") (pintype "passive"))
    )
    (net (code "34") (name "/MCU_RX2") (class "Default")
      (node (ref "RS232_P1") (pin "3") (pinfunction "3_3") (pintype "passive"))
      (node (ref "U5") (pin "9") (pinfunction "R2OUT_9") (pintype "passive"))
    )
    (net (code "35") (name "/MCU_TX1") (class "Default")
      (node (ref "RS232_P1") (pin "2") (pinfunction "2_2") (pintype "passive"))
      (node (ref "U5") (pin "11") (pinfunction "T1IN_11") (pintype "passive"))
    )
    (net (code "36") (name "/MCU_TX2") (class "Default")
      (node (ref "RS232_P1") (pin "4") (pinfunction "4_4") (pintype "passive"))
      (node (ref "U5") (pin "10") (pinfunction "T2IN_10") (pintype "passive"))
    )
    (net (code "37") (name "/PA0") (class "Default")
      (node (ref "AD_P1") (pin "1") (pinfunction "1_1") (pintype "passive"))
      (node (ref "Header A") (pin "1") (pinfunction "1_1") (pintype "passive"))
      (node (ref "U1") (pin "95") (pinfunction "PA0_95") (pintype "passive"))
    )
    (net (code "38") (name "/PA1") (class "Default")
      (node (ref "AD_P1") (pin "2") (pinfunction "2_2") (pintype "passive"))
      (node (ref "Header A") (pin "2") (pinfunction "2_2") (pintype "passive"))
      (node (ref "U1") (pin "96") (pinfunction "PA1_96") (pintype "passive"))
    )
    (net (code "39") (name "/PA2") (class "Default")
      (node (ref "AD_P1") (pin "3") (pinfunction "3_3") (pintype "passive"))
      (node (ref "Header A") (pin "3") (pinfunction "3_3") (pintype "passive"))
      (node (ref "U1") (pin "97") (pinfunction "PA2_97") (pintype "passive"))
    )
    (net (code "40") (name "/PA3") (class "Default")
      (node (ref "Header A") (pin "4") (pinfunction "4_4") (pintype "passive"))
      (node (ref "U1") (pin "98") (pinfunction "PA3_98") (pintype "passive"))
    )
    (net (code "41") (name "/PA4") (class "Default")
      (node (ref "Header A") (pin "5") (pinfunction "5_5") (pintype "passive"))
      (node (ref "U1") (pin "99") (pinfunction "PA4_99") (pintype "passive"))
    )
    (net (code "42") (name "/PA5") (class "Default")
      (node (ref "Header A") (pin "6") (pinfunction "6_6") (pintype "passive"))
      (node (ref "U1") (pin "100") (pinfunction "PA5_100") (pintype "passive"))
    )
    (net (code "43") (name "/PA6") (class "Default")
      (node (ref "Header A") (pin "7") (pinfunction "7_7") (pintype "passive"))
      (node (ref "U1") (pin "1") (pinfunction "PA6_1") (pintype "passive"))
    )
    (net (code "44") (name "/PA7") (class "Default")
      (node (ref "Header A") (pin "8") (pinfunction "8_8") (pintype "passive"))
      (node (ref "U1") (pin "2") (pinfunction "PA7_2") (pintype "passive"))
    )
    (net (code "45") (name "/PB0") (class "Default")
      (node (ref "Header B") (pin "8") (pinfunction "8_8") (pintype "passive"))
      (node (ref "U1") (pin "5") (pinfunction "PB0_5") (pintype "passive"))
    )
    (net (code "46") (name "/PB1") (class "Default")
      (node (ref "Header B") (pin "7") (pinfunction "7_7") (pintype "passive"))
      (node (ref "U1") (pin "6") (pinfunction "PB1_6") (pintype "passive"))
    )
    (net (code "47") (name "/PB2") (class "Default")
      (node (ref "Header B") (pin "6") (pinfunction "6_6") (pintype "passive"))
      (node (ref "U1") (pin "7") (pinfunction "PB2_7") (pintype "passive"))
    )
    (net (code "48") (name "/PB3") (class "Default")
      (node (ref "Header B") (pin "5") (pinfunction "5_5") (pintype "passive"))
      (node (ref "U1") (pin "8") (pinfunction "PB3_8") (pintype "passive"))
    )
    (net (code "49") (name "/PB4") (class "Default")
      (node (ref "Header B") (pin "4") (pinfunction "4_4") (pintype "passive"))
      (node (ref "JTAG") (pin "5") (pinfunction "TMS_5") (pintype "passive"))
      (node (ref "U1") (pin "9") (pinfunction "PB4_9") (pintype "passive"))
    )
    (net (code "50") (name "/PB5") (class "Default")
      (node (ref "Header B") (pin "3") (pinfunction "3_3") (pintype "passive"))
      (node (ref "JTAG") (pin "9") (pinfunction "TDI_9") (pintype "passive"))
      (node (ref "U1") (pin "10") (pinfunction "PB5_10") (pintype "passive"))
    )
    (net (code "51") (name "/PB6") (class "Default")
      (node (ref "Header B") (pin "2") (pinfunction "2_2") (pintype "passive"))
      (node (ref "JTAG") (pin "1") (pinfunction "TCK_1") (pintype "passive"))
      (node (ref "U1") (pin "11") (pinfunction "PB6_11") (pintype "passive"))
    )
    (net (code "52") (name "/PB7") (class "Default")
      (node (ref "Header B") (pin "1") (pinfunction "1_1") (pintype "passive"))
      (node (ref "JTAG") (pin "3") (pinfunction "TDO_3") (pintype "passive"))
      (node (ref "U1") (pin "12") (pinfunction "PB7_12") (pintype "passive"))
    )
    (net (code "53") (name "/PC0") (class "Default")
      (node (ref "Header C") (pin "1") (pinfunction "1_1") (pintype "passive"))
      (node (ref "LED_P2") (pin "4") (pinfunction "4_4") (pintype "passive"))
      (node (ref "U1") (pin "15") (pinfunction "PC0_15") (pintype "passive"))
    )
    (net (code "54") (name "/PC1") (class "Default")
      (node (ref "Header C") (pin "2") (pinfunction "2_2") (pintype "passive"))
      (node (ref "LED_P2") (pin "3") (pinfunction "3_3") (pintype "passive"))
      (node (ref "U1") (pin "16") (pinfunction "PC1_16") (pintype "passive"))
    )
    (net (code "55") (name "/PC2") (class "Default")
      (node (ref "Header C") (pin "3") (pinfunction "3_3") (pintype "passive"))
      (node (ref "LED_P2") (pin "2") (pinfunction "2_2") (pintype "passive"))
      (node (ref "U1") (pin "17") (pinfunction "PC2_17") (pintype "passive"))
    )
    (net (code "56") (name "/PC3") (class "Default")
      (node (ref "Header C") (pin "4") (pinfunction "4_4") (pintype "passive"))
      (node (ref "LED_P2") (pin "1") (pinfunction "1_1") (pintype "passive"))
      (node (ref "U1") (pin "18") (pinfunction "PC3_18") (pintype "passive"))
    )
    (net (code "57") (name "/PC4") (class "Default")
      (node (ref "Header C") (pin "5") (pinfunction "5_5") (pintype "passive"))
      (node (ref "LCD_H2") (pin "1") (pinfunction "1_1") (pintype "passive"))
      (node (ref "U1") (pin "19") (pinfunction "PC4_19") (pintype "passive"))
    )
    (net (code "58") (name "/PC5") (class "Default")
      (node (ref "Header C") (pin "6") (pinfunction "6_6") (pintype "passive"))
      (node (ref "LCD_H2") (pin "2") (pinfunction "2_2") (pintype "passive"))
      (node (ref "U1") (pin "20") (pinfunction "PC5_20") (pintype "passive"))
    )
    (net (code "59") (name "/PC6") (class "Default")
      (node (ref "Header C") (pin "7") (pinfunction "7_7") (pintype "passive"))
      (node (ref "U1") (pin "21") (pinfunction "PC6_21") (pintype "passive"))
    )
    (net (code "60") (name "/PC7") (class "Default")
      (node (ref "Header C") (pin "8") (pinfunction "8_8") (pintype "passive"))
      (node (ref "LCD_H2") (pin "3") (pinfunction "3_3") (pintype "passive"))
      (node (ref "U1") (pin "22") (pinfunction "PC7_22") (pintype "passive"))
    )
    (net (code "61") (name "/PD0") (class "Default")
      (node (ref "Header D") (pin "8") (pinfunction "8_8") (pintype "passive"))
      (node (ref "SPI1_P1") (pin "1") (pinfunction "1_1") (pintype "passive"))
      (node (ref "U1") (pin "25") (pinfunction "PD0_25") (pintype "passive"))
    )
    (net (code "62") (name "/PD1") (class "Default")
      (node (ref "Header D") (pin "7") (pinfunction "7_7") (pintype "passive"))
      (node (ref "SPI1_P1") (pin "2") (pinfunction "2_2") (pintype "passive"))
      (node (ref "U1") (pin "26") (pinfunction "PD1_26") (pintype "passive"))
    )
    (net (code "63") (name "/PD2") (class "Default")
      (node (ref "FT232_P2") (pin "1") (pinfunction "1_1") (pintype "passive"))
      (node (ref "Header D") (pin "6") (pinfunction "6_6") (pintype "passive"))
      (node (ref "U1") (pin "27") (pinfunction "PD2_27") (pintype "passive"))
    )
    (net (code "64") (name "/PD3") (class "Default")
      (node (ref "FT232_P2") (pin "2") (pinfunction "2_2") (pintype "passive"))
      (node (ref "Header D") (pin "5") (pinfunction "5_5") (pintype "passive"))
      (node (ref "U1") (pin "28") (pinfunction "PD3_28") (pintype "passive"))
    )
    (net (code "65") (name "/PD4") (class "Default")
      (node (ref "Header D") (pin "4") (pinfunction "4_4") (pintype "passive"))
      (node (ref "SPI1_P1") (pin "3") (pinfunction "3_3") (pintype "passive"))
      (node (ref "U1") (pin "29") (pinfunction "PD4_29") (pintype "passive"))
    )
    (net (code "66") (name "/PD5") (class "Default")
      (node (ref "Header D") (pin "3") (pinfunction "3_3") (pintype "passive"))
      (node (ref "SPI1_P1") (pin "4") (pinfunction "4_4") (pintype "passive"))
      (node (ref "U1") (pin "30") (pinfunction "PD5_30") (pintype "passive"))
    )
    (net (code "67") (name "/PD6") (class "Default")
      (node (ref "Header D") (pin "2") (pinfunction "2_2") (pintype "passive"))
      (node (ref "SPI1_P1") (pin "5") (pinfunction "5_5") (pintype "passive"))
      (node (ref "U1") (pin "31") (pinfunction "PD6_31") (pintype "passive"))
    )
    (net (code "68") (name "/PD7") (class "Default")
      (node (ref "Header D") (pin "1") (pinfunction "1_1") (pintype "passive"))
      (node (ref "SPI1_P1") (pin "6") (pinfunction "6_6") (pintype "passive"))
      (node (ref "U1") (pin "32") (pinfunction "PD7_32") (pintype "passive"))
    )
    (net (code "69") (name "/PDI_DATA") (class "Default")
      (node (ref "Header X") (pin "4") (pinfunction "4_4") (pintype "passive"))
      (node (ref "PDI") (pin "1") (pinfunction "DATA_1") (pintype "passive"))
      (node (ref "U1") (pin "89") (pinfunction "PDI_DATA_89") (pintype "passive"))
    )
    (net (code "70") (name "/PE0") (class "Default")
      (node (ref "Header E") (pin "1") (pinfunction "1_1") (pintype "passive"))
      (node (ref "Joystick_P2") (pin "1") (pinfunction "1_1") (pintype "passive"))
      (node (ref "U1") (pin "35") (pinfunction "PE0_35") (pintype "passive"))
    )
    (net (code "71") (name "/PE1") (class "Default")
      (node (ref "Header E") (pin "2") (pinfunction "2_2") (pintype "passive"))
      (node (ref "Joystick_P2") (pin "2") (pinfunction "2_2") (pintype "passive"))
      (node (ref "U1") (pin "36") (pinfunction "PE1_36") (pintype "passive"))
    )
    (net (code "72") (name "/PE2") (class "Default")
      (node (ref "Header E") (pin "3") (pinfunction "3_3") (pintype "passive"))
      (node (ref "Joystick_P2") (pin "3") (pinfunction "3_3") (pintype "passive"))
      (node (ref "U1") (pin "37") (pinfunction "PE2_37") (pintype "passive"))
    )
    (net (code "73") (name "/PE3") (class "Default")
      (node (ref "Header E") (pin "4") (pinfunction "4_4") (pintype "passive"))
      (node (ref "Joystick_P2") (pin "4") (pinfunction "4_4") (pintype "passive"))
      (node (ref "U1") (pin "38") (pinfunction "PE3_38") (pintype "passive"))
    )
    (net (code "74") (name "/PE4") (class "Default")
      (node (ref "Header E") (pin "5") (pinfunction "5_5") (pintype "passive"))
      (node (ref "Joystick_P2") (pin "5") (pinfunction "5_5") (pintype "passive"))
      (node (ref "U1") (pin "39") (pinfunction "PE4_39") (pintype "passive"))
    )
    (net (code "75") (name "/PE5") (class "Default")
      (node (ref "Header E") (pin "6") (pinfunction "6_6") (pintype "passive"))
      (node (ref "Key_P2") (pin "1") (pinfunction "1_1") (pintype "passive"))
      (node (ref "U1") (pin "40") (pinfunction "PE5_40") (pintype "passive"))
    )
    (net (code "76") (name "/PE6") (class "Default")
      (node (ref "Header E") (pin "7") (pinfunction "7_7") (pintype "passive"))
      (node (ref "Key_P2") (pin "2") (pinfunction "2_2") (pintype "passive"))
      (node (ref "U1") (pin "41") (pinfunction "PE6_41") (pintype "passive"))
    )
    (net (code "77") (name "/PE7") (class "Default")
      (node (ref "Header E") (pin "8") (pinfunction "8_8") (pintype "passive"))
      (node (ref "Key_P2") (pin "3") (pinfunction "3_3") (pintype "passive"))
      (node (ref "U1") (pin "42") (pinfunction "PE7_42") (pintype "passive"))
    )
    (net (code "78") (name "/PF0") (class "Default")
      (node (ref "Header F") (pin "8") (pinfunction "8_8") (pintype "passive"))
      (node (ref "TWI_P2") (pin "2") (pinfunction "2_2") (pintype "passive"))
      (node (ref "U1") (pin "45") (pinfunction "PF0_45") (pintype "passive"))
    )
    (net (code "79") (name "/PF1") (class "Default")
      (node (ref "Header F") (pin "7") (pinfunction "7_7") (pintype "passive"))
      (node (ref "TWI_P2") (pin "1") (pinfunction "1_1") (pintype "passive"))
      (node (ref "U1") (pin "46") (pinfunction "PF1_46") (pintype "passive"))
    )
    (net (code "80") (name "/PF2") (class "Default")
      (node (ref "Header F") (pin "6") (pinfunction "6_6") (pintype "passive"))
      (node (ref "RS232_P2") (pin "1") (pinfunction "1_1") (pintype "passive"))
      (node (ref "U1") (pin "47") (pinfunction "PF2_47") (pintype "passive"))
      (node (ref "U7_P2") (pin "1") (pinfunction "1_1") (pintype "passive"))
    )
    (net (code "81") (name "/PF3") (class "Default")
      (node (ref "Header F") (pin "5") (pinfunction "5_5") (pintype "passive"))
      (node (ref "RS232_P2") (pin "2") (pinfunction "2_2") (pintype "passive"))
      (node (ref "U1") (pin "48") (pinfunction "PF3_48") (pintype "passive"))
      (node (ref "U7_P2") (pin "2") (pinfunction "2_2") (pintype "passive"))
    )
    (net (code "82") (name "/PF4") (class "Default")
      (node (ref "Buzzer_P1") (pin "1") (pinfunction "1_1") (pintype "passive"))
      (node (ref "Header F") (pin "4") (pinfunction "4_4") (pintype "passive"))
      (node (ref "U1") (pin "49") (pinfunction "PF4_49") (pintype "passive"))
    )
    (net (code "83") (name "/PF5") (class "Default")
      (node (ref "Header F") (pin "3") (pinfunction "3_3") (pintype "passive"))
      (node (ref "U1") (pin "50") (pinfunction "PF5_50") (pintype "passive"))
    )
    (net (code "84") (name "/PF6") (class "Default")
      (node (ref "Header F") (pin "2") (pinfunction "2_2") (pintype "passive"))
      (node (ref "RS232_P2") (pin "3") (pinfunction "3_3") (pintype "passive"))
      (node (ref "U1") (pin "51") (pinfunction "PF6_51") (pintype "passive"))
    )
    (net (code "85") (name "/PF7") (class "Default")
      (node (ref "Header F") (pin "1") (pinfunction "1_1") (pintype "passive"))
      (node (ref "RS232_P2") (pin "4") (pinfunction "4_4") (pintype "passive"))
      (node (ref "U1") (pin "52") (pinfunction "PF7_52") (pintype "passive"))
    )
    (net (code "86") (name "/PH0") (class "Default")
      (node (ref "Header H") (pin "1") (pinfunction "1_1") (pintype "passive"))
      (node (ref "U1") (pin "55") (pinfunction "PH0_55") (pintype "passive"))
      (node (ref "U2") (pin "16") (pinfunction "WE#_16") (pintype "passive"))
    )
    (net (code "87") (name "/PH1") (class "Default")
      (node (ref "Header H") (pin "2") (pinfunction "2_2") (pintype "passive"))
      (node (ref "U1") (pin "56") (pinfunction "PH1_56") (pintype "passive"))
      (node (ref "U2") (pin "17") (pinfunction "CAS#_17") (pintype "passive"))
    )
    (net (code "88") (name "/PH2") (class "Default")
      (node (ref "Header H") (pin "3") (pinfunction "3_3") (pintype "passive"))
      (node (ref "U1") (pin "57") (pinfunction "PH2_57") (pintype "passive"))
      (node (ref "U2") (pin "18") (pinfunction "RAS#_18") (pintype "passive"))
    )
    (net (code "89") (name "/PH3") (class "Default")
      (node (ref "Header H") (pin "4") (pinfunction "4_4") (pintype "passive"))
      (node (ref "U1") (pin "58") (pinfunction "PH3_58") (pintype "passive"))
      (node (ref "U2") (pin "39") (pinfunction "DQM_39") (pintype "passive"))
    )
    (net (code "90") (name "/PH4") (class "Default")
      (node (ref "Header H") (pin "5") (pinfunction "5_5") (pintype "passive"))
      (node (ref "U1") (pin "59") (pinfunction "PH4_59") (pintype "passive"))
      (node (ref "U2") (pin "20") (pinfunction "BA0_20") (pintype "passive"))
    )
    (net (code "91") (name "/PH5") (class "Default")
      (node (ref "Header H") (pin "6") (pinfunction "6_6") (pintype "passive"))
      (node (ref "U1") (pin "60") (pinfunction "PH5_60") (pintype "passive"))
      (node (ref "U2") (pin "21") (pinfunction "BA1_21") (pintype "passive"))
    )
    (net (code "92") (name "/PH6") (class "Default")
      (node (ref "Header H") (pin "7") (pinfunction "7_7") (pintype "passive"))
      (node (ref "U1") (pin "61") (pinfunction "PH6_61") (pintype "passive"))
      (node (ref "U2") (pin "37") (pinfunction "CKE_37") (pintype "passive"))
    )
    (net (code "93") (name "/PH7") (class "Default")
      (node (ref "Header H") (pin "8") (pinfunction "8_8") (pintype "passive"))
      (node (ref "U1") (pin "62") (pinfunction "PH7_62") (pintype "passive"))
      (node (ref "U2") (pin "38") (pinfunction "CLK_38") (pintype "passive"))
    )
    (net (code "94") (name "/PJ0") (class "Default")
      (node (ref "Header J") (pin "8") (pinfunction "8_8") (pintype "passive"))
      (node (ref "U1") (pin "65") (pinfunction "PJ0_65") (pintype "passive"))
      (node (ref "U2") (pin "5") (pinfunction "DQ0_5") (pintype "passive"))
    )
    (net (code "95") (name "/PJ1") (class "Default")
      (node (ref "Header J") (pin "7") (pinfunction "7_7") (pintype "passive"))
      (node (ref "U1") (pin "66") (pinfunction "PJ1_66") (pintype "passive"))
      (node (ref "U2") (pin "11") (pinfunction "DQ1_11") (pintype "passive"))
    )
    (net (code "96") (name "/PJ2") (class "Default")
      (node (ref "Header J") (pin "6") (pinfunction "6_6") (pintype "passive"))
      (node (ref "U1") (pin "67") (pinfunction "PJ2_67") (pintype "passive"))
      (node (ref "U2") (pin "44") (pinfunction "DQ2_44") (pintype "passive"))
    )
    (net (code "97") (name "/PJ3") (class "Default")
      (node (ref "Header J") (pin "5") (pinfunction "5_5") (pintype "passive"))
      (node (ref "U1") (pin "68") (pinfunction "PJ3_68") (pintype "passive"))
      (node (ref "U2") (pin "50") (pinfunction "DQ3_50") (pintype "passive"))
    )
    (net (code "98") (name "/PJ4") (class "Default")
      (node (ref "Header J") (pin "4") (pinfunction "4_4") (pintype "passive"))
      (node (ref "U1") (pin "69") (pinfunction "PJ4_69") (pintype "passive"))
      (node (ref "U2") (pin "33") (pinfunction "A8_33") (pintype "passive"))
    )
    (net (code "99") (name "/PJ5") (class "Default")
      (node (ref "Header J") (pin "3") (pinfunction "3_3") (pintype "passive"))
      (node (ref "U1") (pin "70") (pinfunction "PJ5_70") (pintype "passive"))
      (node (ref "U2") (pin "34") (pinfunction "A9_34") (pintype "passive"))
    )
    (net (code "100") (name "/PJ6") (class "Default")
      (node (ref "Header J") (pin "2") (pinfunction "2_2") (pintype "passive"))
      (node (ref "U1") (pin "71") (pinfunction "PJ6_71") (pintype "passive"))
      (node (ref "U2") (pin "22") (pinfunction "A10_22") (pintype "passive"))
    )
    (net (code "101") (name "/PJ7") (class "Default")
      (node (ref "Header J") (pin "1") (pinfunction "1_1") (pintype "passive"))
      (node (ref "U1") (pin "72") (pinfunction "PJ7_72") (pintype "passive"))
      (node (ref "U2") (pin "35") (pinfunction "A11_35") (pintype "passive"))
    )
    (net (code "102") (name "/PK0") (class "Default")
      (node (ref "Header K") (pin "1") (pinfunction "1_1") (pintype "passive"))
      (node (ref "U1") (pin "75") (pinfunction "PK0_75") (pintype "passive"))
      (node (ref "U2") (pin "23") (pinfunction "A0_23") (pintype "passive"))
    )
    (net (code "103") (name "/PK1") (class "Default")
      (node (ref "Header K") (pin "2") (pinfunction "2_2") (pintype "passive"))
      (node (ref "U1") (pin "76") (pinfunction "PK1_76") (pintype "passive"))
      (node (ref "U2") (pin "24") (pinfunction "A1_24") (pintype "passive"))
    )
    (net (code "104") (name "/PK2") (class "Default")
      (node (ref "Header K") (pin "3") (pinfunction "3_3") (pintype "passive"))
      (node (ref "U1") (pin "77") (pinfunction "PK2_77") (pintype "passive"))
      (node (ref "U2") (pin "25") (pinfunction "A2_25") (pintype "passive"))
    )
    (net (code "105") (name "/PK3") (class "Default")
      (node (ref "Header K") (pin "4") (pinfunction "4_4") (pintype "passive"))
      (node (ref "U1") (pin "78") (pinfunction "PK3_78") (pintype "passive"))
      (node (ref "U2") (pin "26") (pinfunction "A3_26") (pintype "passive"))
    )
    (net (code "106") (name "/PK4") (class "Default")
      (node (ref "Header K") (pin "5") (pinfunction "5_5") (pintype "passive"))
      (node (ref "U1") (pin "79") (pinfunction "PK4_79") (pintype "passive"))
      (node (ref "U2") (pin "29") (pinfunction "A4_29") (pintype "passive"))
    )
    (net (code "107") (name "/PK5") (class "Default")
      (node (ref "Header K") (pin "6") (pinfunction "6_6") (pintype "passive"))
      (node (ref "U1") (pin "80") (pinfunction "PK5_80") (pintype "passive"))
      (node (ref "U2") (pin "30") (pinfunction "A5_30") (pintype "passive"))
    )
    (net (code "108") (name "/PK6") (class "Default")
      (node (ref "Header K") (pin "7") (pinfunction "7_7") (pintype "passive"))
      (node (ref "U1") (pin "81") (pinfunction "PK6_81") (pintype "passive"))
      (node (ref "U2") (pin "31") (pinfunction "A6_31") (pintype "passive"))
    )
    (net (code "109") (name "/PK7") (class "Default")
      (node (ref "Header K") (pin "8") (pinfunction "8_8") (pintype "passive"))
      (node (ref "U1") (pin "82") (pinfunction "PK7_82") (pintype "passive"))
      (node (ref "U2") (pin "32") (pinfunction "A7_32") (pintype "passive"))
    )
    (net (code "110") (name "/PQ0") (class "Default")
      (node (ref "Header X") (pin "8") (pinfunction "8_8") (pintype "passive"))
      (node (ref "U1") (pin "85") (pinfunction "PQ0_85") (pintype "passive"))
    )
    (net (code "111") (name "/PQ1") (class "Default")
      (node (ref "Header X") (pin "7") (pinfunction "7_7") (pintype "passive"))
      (node (ref "U1") (pin "86") (pinfunction "PQ1_86") (pintype "passive"))
    )
    (net (code "112") (name "/PQ2") (class "Default")
      (node (ref "Header X") (pin "6") (pinfunction "6_6") (pintype "passive"))
      (node (ref "U1") (pin "87") (pinfunction "PQ2_87") (pintype "passive"))
    )
    (net (code "113") (name "/PQ3") (class "Default")
      (node (ref "Header X") (pin "5") (pinfunction "5_5") (pintype "passive"))
      (node (ref "SDRAM_P1") (pin "1") (pinfunction "1_1") (pintype "passive"))
      (node (ref "U1") (pin "88") (pinfunction "PQ3_88") (pintype "passive"))
    )
    (net (code "114") (name "/RS232_IN1") (class "Default")
      (node (ref "RS232_1") (pin "3") (pinfunction "3_3") (pintype "passive"))
      (node (ref "U5") (pin "13") (pinfunction "R1IN_13") (pintype "passive"))
    )
    (net (code "115") (name "/RS232_IN2") (class "Default")
      (node (ref "RS232_2") (pin "3") (pinfunction "3_3") (pintype "passive"))
      (node (ref "U5") (pin "8") (pinfunction "R2IN_8") (pintype "passive"))
    )
    (net (code "116") (name "/RS232_OUT1") (class "Default")
      (node (ref "RS232_1") (pin "2") (pinfunction "2_2") (pintype "passive"))
      (node (ref "U5") (pin "14") (pinfunction "T1OUT_14") (pintype "passive"))
    )
    (net (code "117") (name "/RS232_OUT2") (class "Default")
      (node (ref "RS232_2") (pin "2") (pinfunction "2_2") (pintype "passive"))
      (node (ref "U5") (pin "7") (pinfunction "T2OUT_7") (pintype "passive"))
    )
    (net (code "118") (name "/SPI1_CS") (class "Default")
      (node (ref "P3_R6") (pin "1") (pinfunction "1_1") (pintype "passive"))
      (node (ref "SD_CARD1") (pin "10") (pinfunction "10_10") (pintype "passive"))
      (node (ref "SPI1_P2") (pin "3") (pinfunction "3_3") (pintype "passive"))
    )
    (net (code "119") (name "/SPI1_MISO") (class "Default")
      (node (ref "P3_R3") (pin "1") (pinfunction "1_1") (pintype "passive"))
      (node (ref "SD_CARD1") (pin "4") (pinfunction "4_4") (pintype "passive"))
      (node (ref "SPI1_P2") (pin "5") (pinfunction "5_5") (pintype "passive"))
    )
    (net (code "120") (name "/SPI1_MOSI") (class "Default")
      (node (ref "P3_R5") (pin "1") (pinfunction "1_1") (pintype "passive"))
      (node (ref "SD_CARD1") (pin "9") (pinfunction "9_9") (pintype "passive"))
      (node (ref "SPI1_P2") (pin "4") (pinfunction "4_4") (pintype "passive"))
    )
    (net (code "121") (name "/SPI1_SCK") (class "Default")
      (node (ref "P3_R4") (pin "1") (pinfunction "1_1") (pintype "passive"))
      (node (ref "SD_CARD1") (pin "6") (pinfunction "6_6") (pintype "passive"))
      (node (ref "SPI1_P2") (pin "6") (pinfunction "6_6") (pintype "passive"))
    )
    (net (code "122") (name "/TWI1_SCL") (class "Default")
      (node (ref "TWI_P1") (pin "1") (pinfunction "1_1") (pintype "passive"))
      (node (ref "U5_R1") (pin "1") (pinfunction "1_1") (pintype "passive"))
      (node (ref "U6") (pin "6") (pinfunction "SCL_6") (pintype "passive"))
    )
    (net (code "123") (name "/TWI1_SDA") (class "Default")
      (node (ref "TWI_P1") (pin "2") (pinfunction "2_2") (pintype "passive"))
      (node (ref "U5_R2") (pin "1") (pinfunction "1_1") (pintype "passive"))
      (node (ref "U6") (pin "5") (pinfunction "SDA_5") (pintype "passive"))
    )
    (net (code "124") (name "/USBDM") (class "Default")
      (node (ref "U4") (pin "16") (pinfunction "USBDM_16") (pintype "passive"))
      (node (ref "USB_R1") (pin "2") (pinfunction "2_2") (pintype "passive"))
    )
    (net (code "125") (name "/USBDP") (class "Default")
      (node (ref "U4") (pin "15") (pinfunction "USBDP_15") (pintype "passive"))
      (node (ref "USB_R2") (pin "2") (pinfunction "2_2") (pintype "passive"))
    )
    (net (code "126") (name "/WRITEPROTECTn") (class "Default")
      (node (ref "P3_R1") (pin "1") (pinfunction "1_1") (pintype "passive"))
      (node (ref "SD_CARD1") (pin "1") (pinfunction "1_1") (pintype "passive"))
      (node (ref "SPI1_P2") (pin "1") (pinfunction "1_1") (pintype "passive"))
    )
    (net (code "127") (name "/XTAL1") (class "Default")
      (node (ref "U1") (pin "92") (pinfunction "PR1_92") (pintype "passive"))
      (node (ref "XTAL_C2") (pin "2") (pinfunction "2_2") (pintype "passive"))
      (node (ref "Y1") (pin "2") (pinfunction "OSC2_2") (pintype "passive"))
    )
    (net (code "128") (name "/XTAL2") (class "Default")
      (node (ref "U1") (pin "91") (pinfunction "PR0_91") (pintype "passive"))
      (node (ref "XTAL_C1") (pin "2") (pinfunction "2_2") (pintype "passive"))
      (node (ref "Y1") (pin "1") (pinfunction "OSC1_1") (pintype "passive"))
    )
    (net (code "129") (name "/nRST") (class "Default")
      (node (ref "Header X") (pin "3") (pinfunction "3_3") (pintype "passive"))
      (node (ref "JTAG") (pin "6") (pinfunction "nRST_6") (pintype "passive"))
      (node (ref "Key_nRst") (pin "1") (pinfunction "1_1") (pintype "passive"))
      (node (ref "PDI") (pin "5") (pinfunction "CLOCK_5") (pintype "passive"))
      (node (ref "U1") (pin "90") (pinfunction "~{RESET}_/_PDI_CLOCK_90") (pintype "passive"))
      (node (ref "U1_R1") (pin "1") (pinfunction "1_1") (pintype "passive"))
    )
    (net (code "130") (name "3.3V") (class "Default")
      (node (ref "ADJ") (pin "1") (pinfunction "A_1") (pintype "passive"))
      (node (ref "AMS1117-3.3") (pin "2") (pinfunction "Vo_2") (pintype "passive"))
      (node (ref "AVcc.Ind") (pin "1") (pinfunction "0_1") (pintype "passive"))
      (node (ref "Buzzer_R1") (pin "1") (pinfunction "A_1") (pintype "passive"))
      (node (ref "Header X") (pin "1") (pinfunction "1_1") (pintype "passive"))
      (node (ref "J1") (pin "1") (pinfunction "A_1") (pintype "passive"))
      (node (ref "J2") (pin "1") (pinfunction "A_1") (pintype "passive"))
      (node (ref "J3") (pin "1") (pinfunction "A_1") (pintype "passive"))
      (node (ref "JOY_R1") (pin "1") (pinfunction "1_1") (pintype "passive"))
      (node (ref "JOY_R2") (pin "1") (pinfunction "1_1") (pintype "passive"))
      (node (ref "JOY_R3") (pin "1") (pinfunction "1_1") (pintype "passive"))
      (node (ref "JOY_R4") (pin "1") (pinfunction "1_1") (pintype "passive"))
      (node (ref "JOY_R5") (pin "1") (pinfunction "1_1") (pintype "passive"))
      (node (ref "JTAG") (pin "4") (pinfunction "VCC_4") (pintype "passive"))
      (node (ref "Key_R0") (pin "2") (pinfunction "2_2") (pintype "passive"))
      (node (ref "Key_R1") (pin "2") (pinfunction "2_2") (pintype "passive"))
      (node (ref "Key_R2") (pin "2") (pinfunction "2_2") (pintype "passive"))
      (node (ref "LCD_R3") (pin "1") (pinfunction "1_1") (pintype "passive"))
      (node (ref "LCD_R4") (pin "1") (pinfunction "1_1") (pintype "passive"))
      (node (ref "LCD_R5") (pin "1") (pinfunction "1_1") (pintype "passive"))
      (node (ref "LED0") (pin "1") (pinfunction "1_1") (pintype "passive"))
      (node (ref "LED1") (pin "1") (pinfunction "1_1") (pintype "passive"))
      (node (ref "LED2") (pin "1") (pinfunction "1_1") (pintype "passive"))
      (node (ref "LED3") (pin "1") (pinfunction "1_1") (pintype "passive"))
      (node (ref "MCU_C2") (pin "2") (pinfunction "2_2") (pintype "passive"))
      (node (ref "MCU_C3") (pin "2") (pinfunction "2_2") (pintype "passive"))
      (node (ref "MCU_C4") (pin "2") (pinfunction "2_2") (pintype "passive"))
      (node (ref "MCU_C5") (pin "2") (pinfunction "2_2") (pintype "passive"))
      (node (ref "MCU_C6") (pin "2") (pinfunction "2_2") (pintype "passive"))
      (node (ref "MCU_C7") (pin "2") (pinfunction "2_2") (pintype "passive"))
      (node (ref "MCU_C8") (pin "2") (pinfunction "2_2") (pintype "passive"))
      (node (ref "MCU_C9") (pin "2") (pinfunction "2_2") (pintype "passive"))
      (node (ref "P3_C1") (pin "2") (pinfunction "2_2") (pintype "passive"))
      (node (ref "P3_R3") (pin "2") (pinfunction "2_2") (pintype "passive"))
      (node (ref "P3_R4") (pin "2") (pinfunction "2_2") (pintype "passive"))
      (node (ref "P3_R5") (pin "2") (pinfunction "2_2") (pintype "passive"))
      (node (ref "P3_R6") (pin "2") (pinfunction "2_2") (pintype "passive"))
      (node (ref "PDI") (pin "2") (pinfunction "VCC_2") (pintype "passive"))
      (node (ref "POUT1") (pin "1") (pinfunction "1_1") (pintype "passive"))
      (node (ref "POUT1") (pin "2") (pinfunction "2_2") (pintype "passive"))
      (node (ref "POUT1") (pin "3") (pinfunction "3_3") (pintype "passive"))
      (node (ref "POUT1") (pin "4") (pinfunction "4_4") (pintype "passive"))
      (node (ref "POUT1") (pin "5") (pinfunction "5_5") (pintype "passive"))
      (node (ref "POUT1") (pin "6") (pinfunction "6_6") (pintype "passive"))
      (node (ref "POWER_LED") (pin "1") (pinfunction "1_1") (pintype "passive"))
      (node (ref "POW_C1") (pin "2") (pinfunction "2_2") (pintype "passive"))
      (node (ref "POW_C2") (pin "2") (pinfunction "2_2") (pintype "passive"))
      (node (ref "RXLED#") (pin "1") (pinfunction "1_1") (pintype "passive"))
      (node (ref "SDRAM_C1") (pin "1") (pinfunction "1_1") (pintype "passive"))
      (node (ref "SDRAM_C2") (pin "1") (pinfunction "1_1") (pintype "passive"))
      (node (ref "SDRAM_C3") (pin "1") (pinfunction "1_1") (pintype "passive"))
      (node (ref "SDRAM_C4") (pin "1") (pinfunction "1_1") (pintype "passive"))
      (node (ref "SDRAM_C5") (pin "1") (pinfunction "1_1") (pintype "passive"))
      (node (ref "SDRAM_C6") (pin "1") (pinfunction "1_1") (pintype "passive"))
      (node (ref "SDRAM_C7") (pin "1") (pinfunction "1_1") (pintype "passive"))
      (node (ref "SDRAM_R1") (pin "2") (pinfunction "2_2") (pintype "passive"))
      (node (ref "SD_CARD1") (pin "7") (pinfunction "7_7") (pintype "passive"))
      (node (ref "S_C5") (pin "2") (pinfunction "2_2") (pintype "passive"))
      (node (ref "S_R1") (pin "2") (pinfunction "2_2") (pintype "passive"))
      (node (ref "Sensors2") (pin "1") (pinfunction "A_1") (pintype "passive"))
      (node (ref "TXLED#") (pin "1") (pinfunction "1_1") (pintype "passive"))
      (node (ref "U1") (pin "14") (pinfunction "VCC_14") (pintype "passive"))
      (node (ref "U1") (pin "24") (pinfunction "VCC_24") (pintype "passive"))
      (node (ref "U1") (pin "34") (pinfunction "VCC_34") (pintype "passive"))
      (node (ref "U1") (pin "44") (pinfunction "VCC_44") (pintype "passive"))
      (node (ref "U1") (pin "54") (pinfunction "VCC_54") (pintype "passive"))
      (node (ref "U1") (pin "64") (pinfunction "VCC_64") (pintype "passive"))
      (node (ref "U1") (pin "74") (pinfunction "VCC_74") (pintype "passive"))
      (node (ref "U1") (pin "83") (pinfunction "VCC_83") (pintype "passive"))
      (node (ref "U1_R1") (pin "2") (pinfunction "2_2") (pintype "passive"))
      (node (ref "U2") (pin "1") (pinfunction "VDD_1") (pintype "passive"))
      (node (ref "U2") (pin "14") (pinfunction "VDD_14") (pintype "passive"))
      (node (ref "U2") (pin "27") (pinfunction "VDD_27") (pintype "passive"))
      (node (ref "U2") (pin "3") (pinfunction "VDDQ_3") (pintype "passive"))
      (node (ref "U2") (pin "43") (pinfunction "VDDQ_43") (pintype "passive"))
      (node (ref "U2") (pin "49") (pinfunction "VDDQ_49") (pintype "passive"))
      (node (ref "U2") (pin "9") (pinfunction "VDDQ_9") (pintype "passive"))
      (node (ref "U3_C3") (pin "2") (pinfunction "2_2") (pintype "passive"))
      (node (ref "U3_C5") (pin "1") (pinfunction "1_1") (pintype "passive"))
      (node (ref "U4_R1") (pin "1") (pinfunction "1_1") (pintype "passive"))
      (node (ref "U5") (pin "16") (pinfunction "VCC_16") (pintype "passive"))
      (node (ref "U5_C1") (pin "2") (pinfunction "2_2") (pintype "passive"))
      (node (ref "U5_R1") (pin "2") (pinfunction "2_2") (pintype "passive"))
      (node (ref "U5_R2") (pin "2") (pinfunction "2_2") (pintype "passive"))
      (node (ref "U6") (pin "8") (pinfunction "VCC_8") (pintype "passive"))
      (node (ref "U7") (pin "1") (pinfunction "VCC_1") (pintype "passive"))
      (node (ref "U7_C1") (pin "2") (pinfunction "2_2") (pintype "passive"))
      (node (ref "U7_R1") (pin "2") (pinfunction "2_2") (pintype "passive"))
    )
    (net (code "131") (name "5V_A") (class "Default")
      (node (ref "ADJ2") (pin "3") (pinfunction "B_3") (pintype "passive"))
      (node (ref "LCD_C1") (pin "2") (pinfunction "2_2") (pintype "passive"))
      (node (ref "LCD_C2") (pin "2") (pinfunction "2_2") (pintype "passive"))
      (node (ref "LCD_H0") (pin "19") (pinfunction "19_19") (pintype "passive"))
      (node (ref "LCD_H0") (pin "2") (pinfunction "2_2") (pintype "passive"))
      (node (ref "POW_D1") (pin "1") (pinfunction "A_1") (pintype "passive"))
      (node (ref "SW1") (pin "3") (pinfunction "3_3") (pintype "passive"))
      (node (ref "SW1") (pin "6") (pinfunction "6_6") (pintype "passive"))
    )
    (net (code "132") (name "5V_B") (class "Default")
      (node (ref "AMS1117-3.3") (pin "3") (pinfunction "Vi_3") (pintype "output"))
      (node (ref "POW_C3") (pin "2") (pinfunction "2_2") (pintype "passive"))
      (node (ref "POW_D2") (pin "2") (pinfunction "K_2") (pintype "passive"))
      (node (ref "POW_R2") (pin "2") (pinfunction "1_2") (pintype "passive"))
      (node (ref "U4") (pin "20") (pinfunction "VCC_20") (pintype "passive"))
      (node (ref "U4") (pin "4") (pinfunction "VCCIO_4") (pintype "passive"))
      (node (ref "U4_C2") (pin "1") (pinfunction "1_1") (pintype "passive"))
    )
    (net (code "133") (name "GND") (class "Default")
      (node (ref "ADJ") (pin "3") (pinfunction "B_3") (pintype "passive"))
      (node (ref "AMS1117-3.3") (pin "1") (pinfunction "G_1") (pintype "passive"))
      (node (ref "Header X") (pin "2") (pinfunction "2_2") (pintype "passive"))
      (node (ref "J1") (pin "3") (pinfunction "B_3") (pintype "passive"))
      (node (ref "J2") (pin "3") (pinfunction "B_3") (pintype "passive"))
      (node (ref "J3") (pin "3") (pinfunction "B_3") (pintype "passive"))
      (node (ref "JTAG") (pin "10") (pinfunction "GND_10") (pintype "passive"))
      (node (ref "JTAG") (pin "2") (pinfunction "GND_2") (pintype "passive"))
      (node (ref "Joystick1") (pin "5") (pinfunction "COM_5") (pintype "passive"))
      (node (ref "Joystick1") (pin "7") (pinfunction "Shield1_7") (pintype "passive"))
      (node (ref "Joystick1") (pin "8") (pinfunction "Shield2_8") (pintype "passive"))
      (node (ref "Key0") (pin "1") (pinfunction "1_1") (pintype "passive"))
      (node (ref "Key1") (pin "1") (pinfunction "1_1") (pintype "passive"))
      (node (ref "Key2") (pin "1") (pinfunction "1_1") (pintype "passive"))
      (node (ref "Key_nRst") (pin "2") (pinfunction "2_2") (pintype "passive"))
      (node (ref "LCD_C1") (pin "1") (pinfunction "1_1") (pintype "passive"))
      (node (ref "LCD_C2") (pin "1") (pinfunction "1_1") (pintype "passive"))
      (node (ref "LCD_H0") (pin "1") (pinfunction "1_1") (pintype "passive"))
      (node (ref "LCD_H0") (pin "20") (pinfunction "20_20") (pintype "passive"))
      (node (ref "LCD_R6") (pin "1") (pinfunction "1_1") (pintype "passive"))
      (node (ref "MCU_C1") (pin "1") (pinfunction "1_1") (pintype "passive"))
      (node (ref "MCU_C10") (pin "1") (pinfunction "1_1") (pintype "passive"))
      (node (ref "MCU_C2") (pin "1") (pinfunction "1_1") (pintype "passive"))
      (node (ref "MCU_C3") (pin "1") (pinfunction "1_1") (pintype "passive"))
      (node (ref "MCU_C4") (pin "1") (pinfunction "1_1") (pintype "passive"))
      (node (ref "MCU_C5") (pin "1") (pinfunction "1_1") (pintype "passive"))
      (node (ref "MCU_C6") (pin "1") (pinfunction "1_1") (pintype "passive"))
      (node (ref "MCU_C7") (pin "1") (pinfunction "1_1") (pintype "passive"))
      (node (ref "MCU_C8") (pin "1") (pinfunction "1_1") (pintype "passive"))
      (node (ref "MCU_C9") (pin "1") (pinfunction "1_1") (pintype "passive"))
      (node (ref "P2") (pin "5") (pinfunction "GND_5") (pintype "passive"))
      (node (ref "P2") (pin "6") (pinfunction "SHIELD1_6") (pintype "passive"))
      (node (ref "P2") (pin "7") (pinfunction "SHIELD2_7") (pintype "passive"))
      (node (ref "P2") (pin "8") (pinfunction "SHIELD3_8") (pintype "passive"))
      (node (ref "P2") (pin "9") (pinfunction "SHIELD4_9") (pintype "passive"))
      (node (ref "P3_C1") (pin "1") (pinfunction "1_1") (pintype "passive"))
      (node (ref "P3_R1") (pin "2") (pinfunction "2_2") (pintype "passive"))
      (node (ref "P3_R2") (pin "2") (pinfunction "2_2") (pintype "passive"))
      (node (ref "PDI") (pin "6") (pinfunction "GND_6") (pintype "passive"))
      (node (ref "POUT2") (pin "1") (pinfunction "1_1") (pintype "passive"))
      (node (ref "POUT2") (pin "2") (pinfunction "2_2") (pintype "passive"))
      (node (ref "POUT2") (pin "3") (pinfunction "3_3") (pintype "passive"))
      (node (ref "POUT2") (pin "4") (pinfunction "4_4") (pintype "passive"))
      (node (ref "POUT2") (pin "5") (pinfunction "5_5") (pintype "passive"))
      (node (ref "POUT2") (pin "6") (pinfunction "6_6") (pintype "passive"))
      (node (ref "POW_C1") (pin "1") (pinfunction "1_1") (pintype "passive"))
      (node (ref "POW_C2") (pin "1") (pinfunction "1_1") (pintype "passive"))
      (node (ref "POW_C3") (pin "1") (pinfunction "1_1") (pintype "passive"))
      (node (ref "POW_D2") (pin "1") (pinfunction "A_1") (pintype "passive"))
      (node (ref "POW_R1") (pin "1") (pinfunction "1_1") (pintype "passive"))
      (node (ref "Power5") (pin "2") (pinfunction "G_2") (pintype "passive"))
      (node (ref "RS232_1") (pin "10") (pinfunction "MH1_10") (pintype "passive"))
      (node (ref "RS232_1") (pin "11") (pinfunction "MH2_11") (pintype "passive"))
      (node (ref "RS232_1") (pin "5") (pinfunction "5_5") (pintype "passive"))
      (node (ref "RS232_2") (pin "10") (pinfunction "MH1_10") (pintype "passive"))
      (node (ref "RS232_2") (pin "11") (pinfunction "MH2_11") (pintype "passive"))
      (node (ref "RS232_2") (pin "5") (pinfunction "5_5") (pintype "passive"))
      (node (ref "SDRAM_C1") (pin "2") (pinfunction "2_2") (pintype "passive"))
      (node (ref "SDRAM_C2") (pin "2") (pinfunction "2_2") (pintype "passive"))
      (node (ref "SDRAM_C3") (pin "2") (pinfunction "2_2") (pintype "passive"))
      (node (ref "SDRAM_C4") (pin "2") (pinfunction "2_2") (pintype "passive"))
      (node (ref "SDRAM_C5") (pin "2") (pinfunction "2_2") (pintype "passive"))
      (node (ref "SDRAM_C6") (pin "2") (pinfunction "2_2") (pintype "passive"))
      (node (ref "SDRAM_C7") (pin "2") (pinfunction "2_2") (pintype "passive"))
      (node (ref "SDRAM_P1") (pin "3") (pinfunction "3_3") (pintype "passive"))
      (node (ref "SD_CARD1") (pin "12") (pinfunction "12_12") (pintype "passive"))
      (node (ref "SD_CARD1") (pin "13") (pinfunction "13_13") (pintype "passive"))
      (node (ref "SD_CARD1") (pin "14") (pinfunction "14_14") (pintype "passive"))
      (node (ref "SD_CARD1") (pin "15") (pinfunction "15_15") (pintype "passive"))
      (node (ref "SD_CARD1") (pin "5") (pinfunction "5_5") (pintype "passive"))
      (node (ref "SD_CARD1") (pin "8") (pinfunction "8_8") (pintype "passive"))
      (node (ref "S_C5") (pin "1") (pinfunction "1_1") (pintype "passive"))
      (node (ref "S_R2") (pin "1") (pinfunction "1_1") (pintype "passive"))
      (node (ref "Sensors3") (pin "2") (pinfunction "2_2") (pintype "passive"))
      (node (ref "U1") (pin "13") (pinfunction "GND_13") (pintype "passive"))
      (node (ref "U1") (pin "23") (pinfunction "GND_23") (pintype "passive"))
      (node (ref "U1") (pin "3") (pinfunction "GND_3") (pintype "passive"))
      (node (ref "U1") (pin "33") (pinfunction "GND_33") (pintype "passive"))
      (node (ref "U1") (pin "43") (pinfunction "GND_43") (pintype "passive"))
      (node (ref "U1") (pin "53") (pinfunction "GND_53") (pintype "passive"))
      (node (ref "U1") (pin "63") (pinfunction "GND_63") (pintype "passive"))
      (node (ref "U1") (pin "73") (pinfunction "GND_73") (pintype "passive"))
      (node (ref "U1") (pin "84") (pinfunction "GND_84") (pintype "passive"))
      (node (ref "U1") (pin "93") (pinfunction "GND_93") (pintype "passive"))
      (node (ref "U2") (pin "12") (pinfunction "VSSQ_12") (pintype "passive"))
      (node (ref "U2") (pin "28") (pinfunction "VSS_28") (pintype "passive"))
      (node (ref "U2") (pin "41") (pinfunction "VSS_41") (pintype "passive"))
      (node (ref "U2") (pin "46") (pinfunction "VSSQ_46") (pintype "passive"))
      (node (ref "U2") (pin "52") (pinfunction "VSSQ_52") (pintype "passive"))
      (node (ref "U2") (pin "54") (pinfunction "VSS_54") (pintype "passive"))
      (node (ref "U2") (pin "6") (pinfunction "VSSQ_6") (pintype "passive"))
      (node (ref "U3_C4") (pin "1") (pinfunction "1_1") (pintype "passive"))
      (node (ref "U3_C5") (pin "2") (pinfunction "2_2") (pintype "passive"))
      (node (ref "U4") (pin "18") (pinfunction "GND_18") (pintype "passive"))
      (node (ref "U4") (pin "21") (pinfunction "GND_21") (pintype "passive"))
      (node (ref "U4") (pin "25") (pinfunction "AGND_25") (pintype "passive"))
      (node (ref "U4") (pin "26") (pinfunction "TEST_26") (pintype "passive"))
      (node (ref "U4") (pin "7") (pinfunction "GND_7") (pintype "passive"))
      (node (ref "U4_C1") (pin "1") (pinfunction "1_1") (pintype "passive"))
      (node (ref "U4_C2") (pin "2") (pinfunction "2_2") (pintype "passive"))
      (node (ref "U5") (pin "15") (pinfunction "GND_15") (pintype "passive"))
      (node (ref "U5_C1") (pin "1") (pinfunction "1_1") (pintype "passive"))
      (node (ref "U6") (pin "4") (pinfunction "GND_4") (pintype "passive"))
      (node (ref "U6") (pin "7") (pinfunction "WP_7") (pintype "passive"))
      (node (ref "U7") (pin "11") (pinfunction "GND_11") (pintype "passive"))
      (node (ref "U7") (pin "2") (pinfunction "AGND_2") (pintype "passive"))
      (node (ref "U7") (pin "3") (pinfunction "SEL_3") (pintype "passive"))
      (node (ref "U7") (pin "4") (pinfunction "MD0_4") (pintype "passive"))
      (node (ref "U7") (pin "5") (pinfunction "MD1_5") (pintype "passive"))
      (node (ref "U7") (pin "7") (pinfunction "GND_7") (pintype "passive"))
      (node (ref "U7_C1") (pin "1") (pinfunction "1_1") (pintype "passive"))
      (node (ref "XTAL_C1") (pin "1") (pinfunction "1_1") (pintype "passive"))
      (node (ref "XTAL_C2") (pin "1") (pinfunction "1_1") (pintype "passive"))
    )
    (net (code "134") (name "Net-(ADJ2-A)") (class "Default")
      (node (ref "ADJ2") (pin "1") (pinfunction "A_1") (pintype "passive"))
      (node (ref "LCD_H0") (pin "18") (pinfunction "18_18") (pintype "passive"))
    )
    (net (code "135") (name "Net-(ADJ2-TAP)") (class "Default")
      (node (ref "ADJ2") (pin "2") (pinfunction "TAP_2") (pintype "passive"))
      (node (ref "LCD_H0") (pin "3") (pinfunction "3_3") (pintype "passive"))
    )
    (net (code "136") (name "Net-(B1-0)") (class "Default")
      (node (ref "B1") (pin "1") (pinfunction "0_1") (pintype "passive"))
      (node (ref "Buzzer_P1") (pin "2") (pinfunction "2_2") (pintype "passive"))
    )
    (net (code "137") (name "Net-(B1-1)") (class "Default")
      (node (ref "B1") (pin "2") (pinfunction "1_2") (pintype "passive"))
      (node (ref "Buzzer_R1") (pin "2") (pinfunction "TAP_2") (pintype "passive"))
    )
    (net (code "138") (name "Net-(J1-COM)") (class "Default")
      (node (ref "J1") (pin "2") (pinfunction "COM_2") (pintype "passive"))
      (node (ref "U6") (pin "1") (pinfunction "A0_1") (pintype "passive"))
    )
    (net (code "139") (name "Net-(J2-COM)") (class "Default")
      (node (ref "J2") (pin "2") (pinfunction "COM_2") (pintype "passive"))
      (node (ref "U6") (pin "2") (pinfunction "A1_2") (pintype "passive"))
    )
    (net (code "140") (name "Net-(J3-COM)") (class "Default")
      (node (ref "J3") (pin "2") (pinfunction "COM_2") (pintype "passive"))
      (node (ref "U6") (pin "3") (pinfunction "A2_3") (pintype "passive"))
    )
    (net (code "141") (name "Net-(LED0-Pad2)") (class "Default")
      (node (ref "LED0") (pin "2") (pinfunction "2_2") (pintype "passive"))
      (node (ref "LED_R0") (pin "2") (pinfunction "2_2") (pintype "passive"))
    )
    (net (code "142") (name "Net-(LED1-Pad2)") (class "Default")
      (node (ref "LED1") (pin "2") (pinfunction "2_2") (pintype "passive"))
      (node (ref "LED_R1") (pin "2") (pinfunction "2_2") (pintype "passive"))
    )
    (net (code "143") (name "Net-(LED2-Pad2)") (class "Default")
      (node (ref "LED2") (pin "2") (pinfunction "2_2") (pintype "passive"))
      (node (ref "LED_R2") (pin "2") (pinfunction "2_2") (pintype "passive"))
    )
    (net (code "144") (name "Net-(LED3-Pad2)") (class "Default")
      (node (ref "LED3") (pin "2") (pinfunction "2_2") (pintype "passive"))
      (node (ref "LED_R3") (pin "2") (pinfunction "2_2") (pintype "passive"))
    )
    (net (code "145") (name "Net-(P2-D+)") (class "Default")
      (node (ref "P2") (pin "3") (pinfunction "D+_3") (pintype "passive"))
      (node (ref "USB_R2") (pin "1") (pinfunction "1_1") (pintype "passive"))
    )
    (net (code "146") (name "Net-(P2-D-)") (class "Default")
      (node (ref "P2") (pin "2") (pinfunction "D-_2") (pintype "passive"))
      (node (ref "USB_R1") (pin "1") (pinfunction "1_1") (pintype "passive"))
    )
    (net (code "147") (name "Net-(POWER_LED-Pad2)") (class "Default")
      (node (ref "POWER_LED") (pin "2") (pinfunction "2_2") (pintype "passive"))
      (node (ref "POW_R1") (pin "2") (pinfunction "2_2") (pintype "passive"))
    )
    (net (code "148") (name "Net-(POW_D1-K)") (class "Default")
      (node (ref "POW_D1") (pin "2") (pinfunction "K_2") (pintype "passive"))
      (node (ref "POW_R2") (pin "1") (pinfunction "0_1") (pintype "passive"))
    )
    (net (code "149") (name "Net-(RXLED#-Pad2)") (class "Default")
      (node (ref "RXLED#") (pin "2") (pinfunction "2_2") (pintype "passive"))
      (node (ref "U4_R3") (pin "1") (pinfunction "1_1") (pintype "passive"))
    )
    (net (code "150") (name "Net-(TXLED#-Pad2)") (class "Default")
      (node (ref "TXLED#") (pin "2") (pinfunction "2_2") (pintype "passive"))
      (node (ref "U4_R2") (pin "1") (pinfunction "1_1") (pintype "passive"))
    )
    (net (code "151") (name "Net-(U2-CS#)") (class "Default")
      (node (ref "SDRAM_P1") (pin "2") (pinfunction "2_2") (pintype "passive"))
      (node (ref "SDRAM_R1") (pin "1") (pinfunction "1_1") (pintype "passive"))
      (node (ref "U2") (pin "19") (pinfunction "CS#_19") (pintype "passive"))
    )
    (net (code "152") (name "Net-(U4-3V3OUT)") (class "Default")
      (node (ref "U4") (pin "17") (pinfunction "3V3OUT_17") (pintype "passive"))
      (node (ref "U4_C1") (pin "2") (pinfunction "2_2") (pintype "passive"))
    )
    (net (code "153") (name "Net-(U4-CBUS0)") (class "Default")
      (node (ref "U4") (pin "23") (pinfunction "CBUS0_23") (pintype "passive"))
      (node (ref "U4_R3") (pin "2") (pinfunction "2_2") (pintype "passive"))
    )
    (net (code "154") (name "Net-(U4-CBUS1)") (class "Default")
      (node (ref "U4") (pin "22") (pinfunction "CBUS1_22") (pintype "passive"))
      (node (ref "U4_R2") (pin "2") (pinfunction "2_2") (pintype "passive"))
    )
    (net (code "155") (name "Net-(U4-CBUS3)") (class "Default")
      (node (ref "U4") (pin "14") (pinfunction "CBUS3_14") (pintype "passive"))
      (node (ref "U4_R1") (pin "2") (pinfunction "2_2") (pintype "passive"))
    )
    (net (code "156") (name "Net-(U5-C1+)") (class "Default")
      (node (ref "U3_C1") (pin "1") (pinfunction "1_1") (pintype "passive"))
      (node (ref "U5") (pin "1") (pinfunction "C1+_1") (pintype "passive"))
    )
    (net (code "157") (name "Net-(U5-C1-)") (class "Default")
      (node (ref "U3_C1") (pin "2") (pinfunction "2_2") (pintype "passive"))
      (node (ref "U5") (pin "3") (pinfunction "C1-_3") (pintype "passive"))
    )
    (net (code "158") (name "Net-(U5-C2+)") (class "Default")
      (node (ref "U3_C2") (pin "1") (pinfunction "1_1") (pintype "passive"))
      (node (ref "U5") (pin "4") (pinfunction "C2+_4") (pintype "passive"))
    )
    (net (code "159") (name "Net-(U5-C2-)") (class "Default")
      (node (ref "U3_C2") (pin "2") (pinfunction "2_2") (pintype "passive"))
      (node (ref "U5") (pin "5") (pinfunction "C2-_5") (pintype "passive"))
    )
    (net (code "160") (name "Net-(U5-V+)") (class "Default")
      (node (ref "U3_C3") (pin "1") (pinfunction "1_1") (pintype "passive"))
      (node (ref "U5") (pin "2") (pinfunction "V+_2") (pintype "passive"))
    )
    (net (code "161") (name "Net-(U5-V-)") (class "Default")
      (node (ref "U3_C4") (pin "2") (pinfunction "2_2") (pintype "passive"))
      (node (ref "U5") (pin "6") (pinfunction "V-_6") (pintype "passive"))
    )
    (net (code "162") (name "Net-(U7-LEDA)") (class "Default")
      (node (ref "U7") (pin "10") (pinfunction "LEDA_10") (pintype "passive"))
      (node (ref "U7_R1") (pin "1") (pinfunction "1_1") (pintype "passive"))
    )
    (net (code "163") (name "Net-(U7-RXD)") (class "Default")
      (node (ref "U7") (pin "8") (pinfunction "RXD_8") (pintype "passive"))
      (node (ref "U7_P1") (pin "1") (pinfunction "1_1") (pintype "passive"))
    )
    (net (code "164") (name "Net-(U7-TXD)") (class "Default")
      (node (ref "U7") (pin "9") (pinfunction "TXD_9") (pintype "passive"))
      (node (ref "U7_P1") (pin "2") (pinfunction "2_2") (pintype "passive"))
    )
    (net (code "165") (name "VBUS") (class "Default")
      (node (ref "P2") (pin "1") (pinfunction "VBUS_1") (pintype "passive"))
      (node (ref "SW1") (pin "1") (pinfunction "1_1") (pintype "passive"))
      (node (ref "SW1") (pin "8") (pinfunction "8_8") (pintype "passive"))
    )
    (net (code "166") (name "VIN") (class "Default")
      (node (ref "Power5") (pin "1") (pinfunction "V_1") (pintype "passive"))
      (node (ref "SW1") (pin "4") (pinfunction "4_4") (pintype "passive"))
      (node (ref "SW1") (pin "5") (pinfunction "5_5") (pintype "passive"))
    )
    (net (code "167") (name "unconnected-(Buzzer_R1-B-Pad3)") (class "Default")
      (node (ref "Buzzer_R1") (pin "3") (pinfunction "B_3") (pintype "passive"))
    )
    (net (code "168") (name "unconnected-(JTAG-NC-Pad7)") (class "Default")
      (node (ref "JTAG") (pin "7") (pinfunction "NC_7") (pintype "passive"))
    )
    (net (code "169") (name "unconnected-(JTAG-NC-Pad8)") (class "Default")
      (node (ref "JTAG") (pin "8") (pinfunction "NC_8") (pintype "passive"))
    )
    (net (code "170") (name "unconnected-(LCD_H0-Pad17)") (class "Default")
      (node (ref "LCD_H0") (pin "17") (pinfunction "17_17") (pintype "passive"))
    )
    (net (code "171") (name "unconnected-(P2-ID-Pad4)") (class "Default")
      (node (ref "P2") (pin "4") (pinfunction "ID_4") (pintype "passive"))
    )
    (net (code "172") (name "unconnected-(PDI-NC-Pad3)") (class "Default")
      (node (ref "PDI") (pin "3") (pinfunction "NC_3") (pintype "passive"))
    )
    (net (code "173") (name "unconnected-(PDI-NC-Pad4)") (class "Default")
      (node (ref "PDI") (pin "4") (pinfunction "NC_4") (pintype "passive"))
    )
    (net (code "174") (name "unconnected-(RS232_1-Pad1)") (class "Default")
      (node (ref "RS232_1") (pin "1") (pinfunction "1_1") (pintype "passive"))
    )
    (net (code "175") (name "unconnected-(RS232_1-Pad4)") (class "Default")
      (node (ref "RS232_1") (pin "4") (pinfunction "4_4") (pintype "passive"))
    )
    (net (code "176") (name "unconnected-(RS232_1-Pad6)") (class "Default")
      (node (ref "RS232_1") (pin "6") (pinfunction "6_6") (pintype "passive"))
    )
    (net (code "177") (name "unconnected-(RS232_1-Pad7)") (class "Default")
      (node (ref "RS232_1") (pin "7") (pinfunction "7_7") (pintype "passive"))
    )
    (net (code "178") (name "unconnected-(RS232_1-Pad8)") (class "Default")
      (node (ref "RS232_1") (pin "8") (pinfunction "8_8") (pintype "passive"))
    )
    (net (code "179") (name "unconnected-(RS232_1-Pad9)") (class "Default")
      (node (ref "RS232_1") (pin "9") (pinfunction "9_9") (pintype "passive"))
    )
    (net (code "180") (name "unconnected-(RS232_2-Pad1)") (class "Default")
      (node (ref "RS232_2") (pin "1") (pinfunction "1_1") (pintype "passive"))
    )
    (net (code "181") (name "unconnected-(RS232_2-Pad4)") (class "Default")
      (node (ref "RS232_2") (pin "4") (pinfunction "4_4") (pintype "passive"))
    )
    (net (code "182") (name "unconnected-(RS232_2-Pad6)") (class "Default")
      (node (ref "RS232_2") (pin "6") (pinfunction "6_6") (pintype "passive"))
    )
    (net (code "183") (name "unconnected-(RS232_2-Pad7)") (class "Default")
      (node (ref "RS232_2") (pin "7") (pinfunction "7_7") (pintype "passive"))
    )
    (net (code "184") (name "unconnected-(RS232_2-Pad8)") (class "Default")
      (node (ref "RS232_2") (pin "8") (pinfunction "8_8") (pintype "passive"))
    )
    (net (code "185") (name "unconnected-(RS232_2-Pad9)") (class "Default")
      (node (ref "RS232_2") (pin "9") (pinfunction "9_9") (pintype "passive"))
    )
    (net (code "186") (name "unconnected-(SD_CARD1-Pad3)") (class "Default")
      (node (ref "SD_CARD1") (pin "3") (pinfunction "3_3") (pintype "passive"))
    )
    (net (code "187") (name "unconnected-(SD_CARD1-Pad11)") (class "Default")
      (node (ref "SD_CARD1") (pin "11") (pinfunction "11_11") (pintype "passive"))
    )
    (net (code "188") (name "unconnected-(SW1-Pad2)") (class "Default")
      (node (ref "SW1") (pin "2") (pinfunction "2_2") (pintype "passive"))
    )
    (net (code "189") (name "unconnected-(SW1-Pad7)") (class "Default")
      (node (ref "SW1") (pin "7") (pinfunction "7_7") (pintype "passive"))
    )
    (net (code "190") (name "unconnected-(U2-NC-Pad2)") (class "Default")
      (node (ref "U2") (pin "2") (pinfunction "NC_2") (pintype "passive"))
    )
    (net (code "191") (name "unconnected-(U2-NC-Pad4)") (class "Default")
      (node (ref "U2") (pin "4") (pinfunction "NC_4") (pintype "passive"))
    )
    (net (code "192") (name "unconnected-(U2-NC-Pad7)") (class "Default")
      (node (ref "U2") (pin "7") (pinfunction "NC_7") (pintype "passive"))
    )
    (net (code "193") (name "unconnected-(U2-NC-Pad8)") (class "Default")
      (node (ref "U2") (pin "8") (pinfunction "NC_8") (pintype "passive"))
    )
    (net (code "194") (name "unconnected-(U2-NC-Pad10)") (class "Default")
      (node (ref "U2") (pin "10") (pinfunction "NC_10") (pintype "passive"))
    )
    (net (code "195") (name "unconnected-(U2-NC-Pad13)") (class "Default")
      (node (ref "U2") (pin "13") (pinfunction "NC_13") (pintype "passive"))
    )
    (net (code "196") (name "unconnected-(U2-NC-Pad15)") (class "Default")
      (node (ref "U2") (pin "15") (pinfunction "NC_15") (pintype "passive"))
    )
    (net (code "197") (name "unconnected-(U2-NC-Pad36)") (class "Default")
      (node (ref "U2") (pin "36") (pinfunction "NC_36") (pintype "passive"))
    )
    (net (code "198") (name "unconnected-(U2-NC-Pad40)") (class "Default")
      (node (ref "U2") (pin "40") (pinfunction "NC_40") (pintype "passive"))
    )
    (net (code "199") (name "unconnected-(U2-NC-Pad42)") (class "Default")
      (node (ref "U2") (pin "42") (pinfunction "NC_42") (pintype "passive"))
    )
    (net (code "200") (name "unconnected-(U2-NC-Pad45)") (class "Default")
      (node (ref "U2") (pin "45") (pinfunction "NC_45") (pintype "passive"))
    )
    (net (code "201") (name "unconnected-(U2-NC-Pad47)") (class "Default")
      (node (ref "U2") (pin "47") (pinfunction "NC_47") (pintype "passive"))
    )
    (net (code "202") (name "unconnected-(U2-NC-Pad48)") (class "Default")
      (node (ref "U2") (pin "48") (pinfunction "NC_48") (pintype "passive"))
    )
    (net (code "203") (name "unconnected-(U2-NC-Pad51)") (class "Default")
      (node (ref "U2") (pin "51") (pinfunction "NC_51") (pintype "passive"))
    )
    (net (code "204") (name "unconnected-(U2-NC-Pad53)") (class "Default")
      (node (ref "U2") (pin "53") (pinfunction "NC_53") (pintype "passive"))
    )
    (net (code "205") (name "unconnected-(U4-CBUS2-Pad13)") (class "Default")
      (node (ref "U4") (pin "13") (pinfunction "CBUS2_13") (pintype "passive"))
    )
    (net (code "206") (name "unconnected-(U4-CBUS4-Pad12)") (class "Default")
      (node (ref "U4") (pin "12") (pinfunction "CBUS4_12") (pintype "passive"))
    )
    (net (code "207") (name "unconnected-(U4-CTS#-Pad11)") (class "Default")
      (node (ref "U4") (pin "11") (pinfunction "CTS#_11") (pintype "passive"))
    )
    (net (code "208") (name "unconnected-(U4-DCD#-Pad10)") (class "Default")
      (node (ref "U4") (pin "10") (pinfunction "DCD#_10") (pintype "passive"))
    )
    (net (code "209") (name "unconnected-(U4-DSR#-Pad9)") (class "Default")
      (node (ref "U4") (pin "9") (pinfunction "DSR#_9") (pintype "passive"))
    )
    (net (code "210") (name "unconnected-(U4-DTR#-Pad2)") (class "Default")
      (node (ref "U4") (pin "2") (pinfunction "DTR#_2") (pintype "passive"))
    )
    (net (code "211") (name "unconnected-(U4-NC-Pad8)") (class "Default")
      (node (ref "U4") (pin "8") (pinfunction "NC_8") (pintype "passive"))
    )
    (net (code "212") (name "unconnected-(U4-NC-Pad24)") (class "Default")
      (node (ref "U4") (pin "24") (pinfunction "NC_24") (pintype "passive"))
    )
    (net (code "213") (name "unconnected-(U4-OSC0-Pad28)") (class "Default")
      (node (ref "U4") (pin "28") (pinfunction "OSC0_28") (pintype "passive"))
    )
    (net (code "214") (name "unconnected-(U4-OSC1-Pad27)") (class "Default")
      (node (ref "U4") (pin "27") (pinfunction "OSC1_27") (pintype "passive"))
    )
    (net (code "215") (name "unconnected-(U4-RESET#-Pad19)") (class "Default")
      (node (ref "U4") (pin "19") (pinfunction "RESET#_19") (pintype "passive"))
    )
    (net (code "216") (name "unconnected-(U4-RI#-Pad6)") (class "Default")
      (node (ref "U4") (pin "6") (pinfunction "RI#_6") (pintype "passive"))
    )
    (net (code "217") (name "unconnected-(U4-RTS#-Pad3)") (class "Default")
      (node (ref "U4") (pin "3") (pinfunction "RTS#_3") (pintype "passive"))
    )
    (net (code "218") (name "unconnected-(U7-NC-Pad6)") (class "Default")
      (node (ref "U7") (pin "6") (pinfunction "NC_6") (pintype "passive"))
    )
  )
)
